# Sheet1.net
KiCad netlist of a schematic drawn in Altium Designer
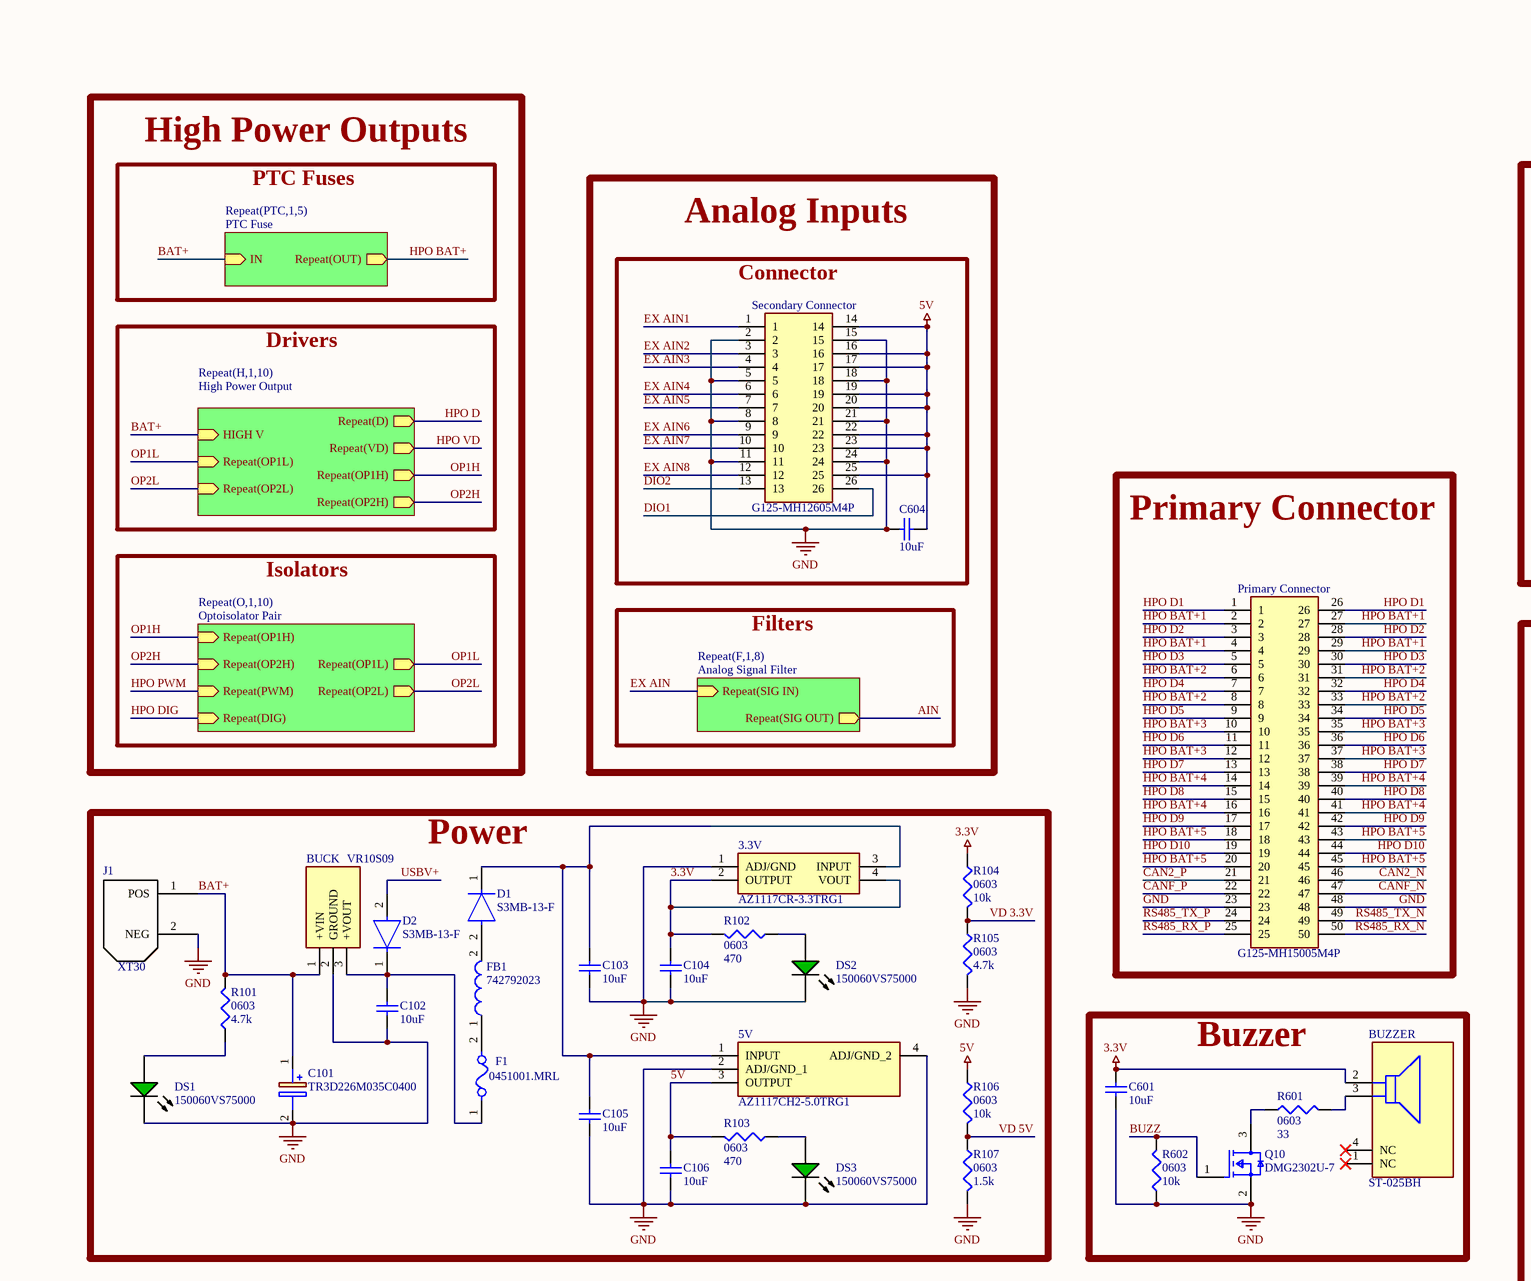
[diagram p0: Sheet1.SchDoc, top left]
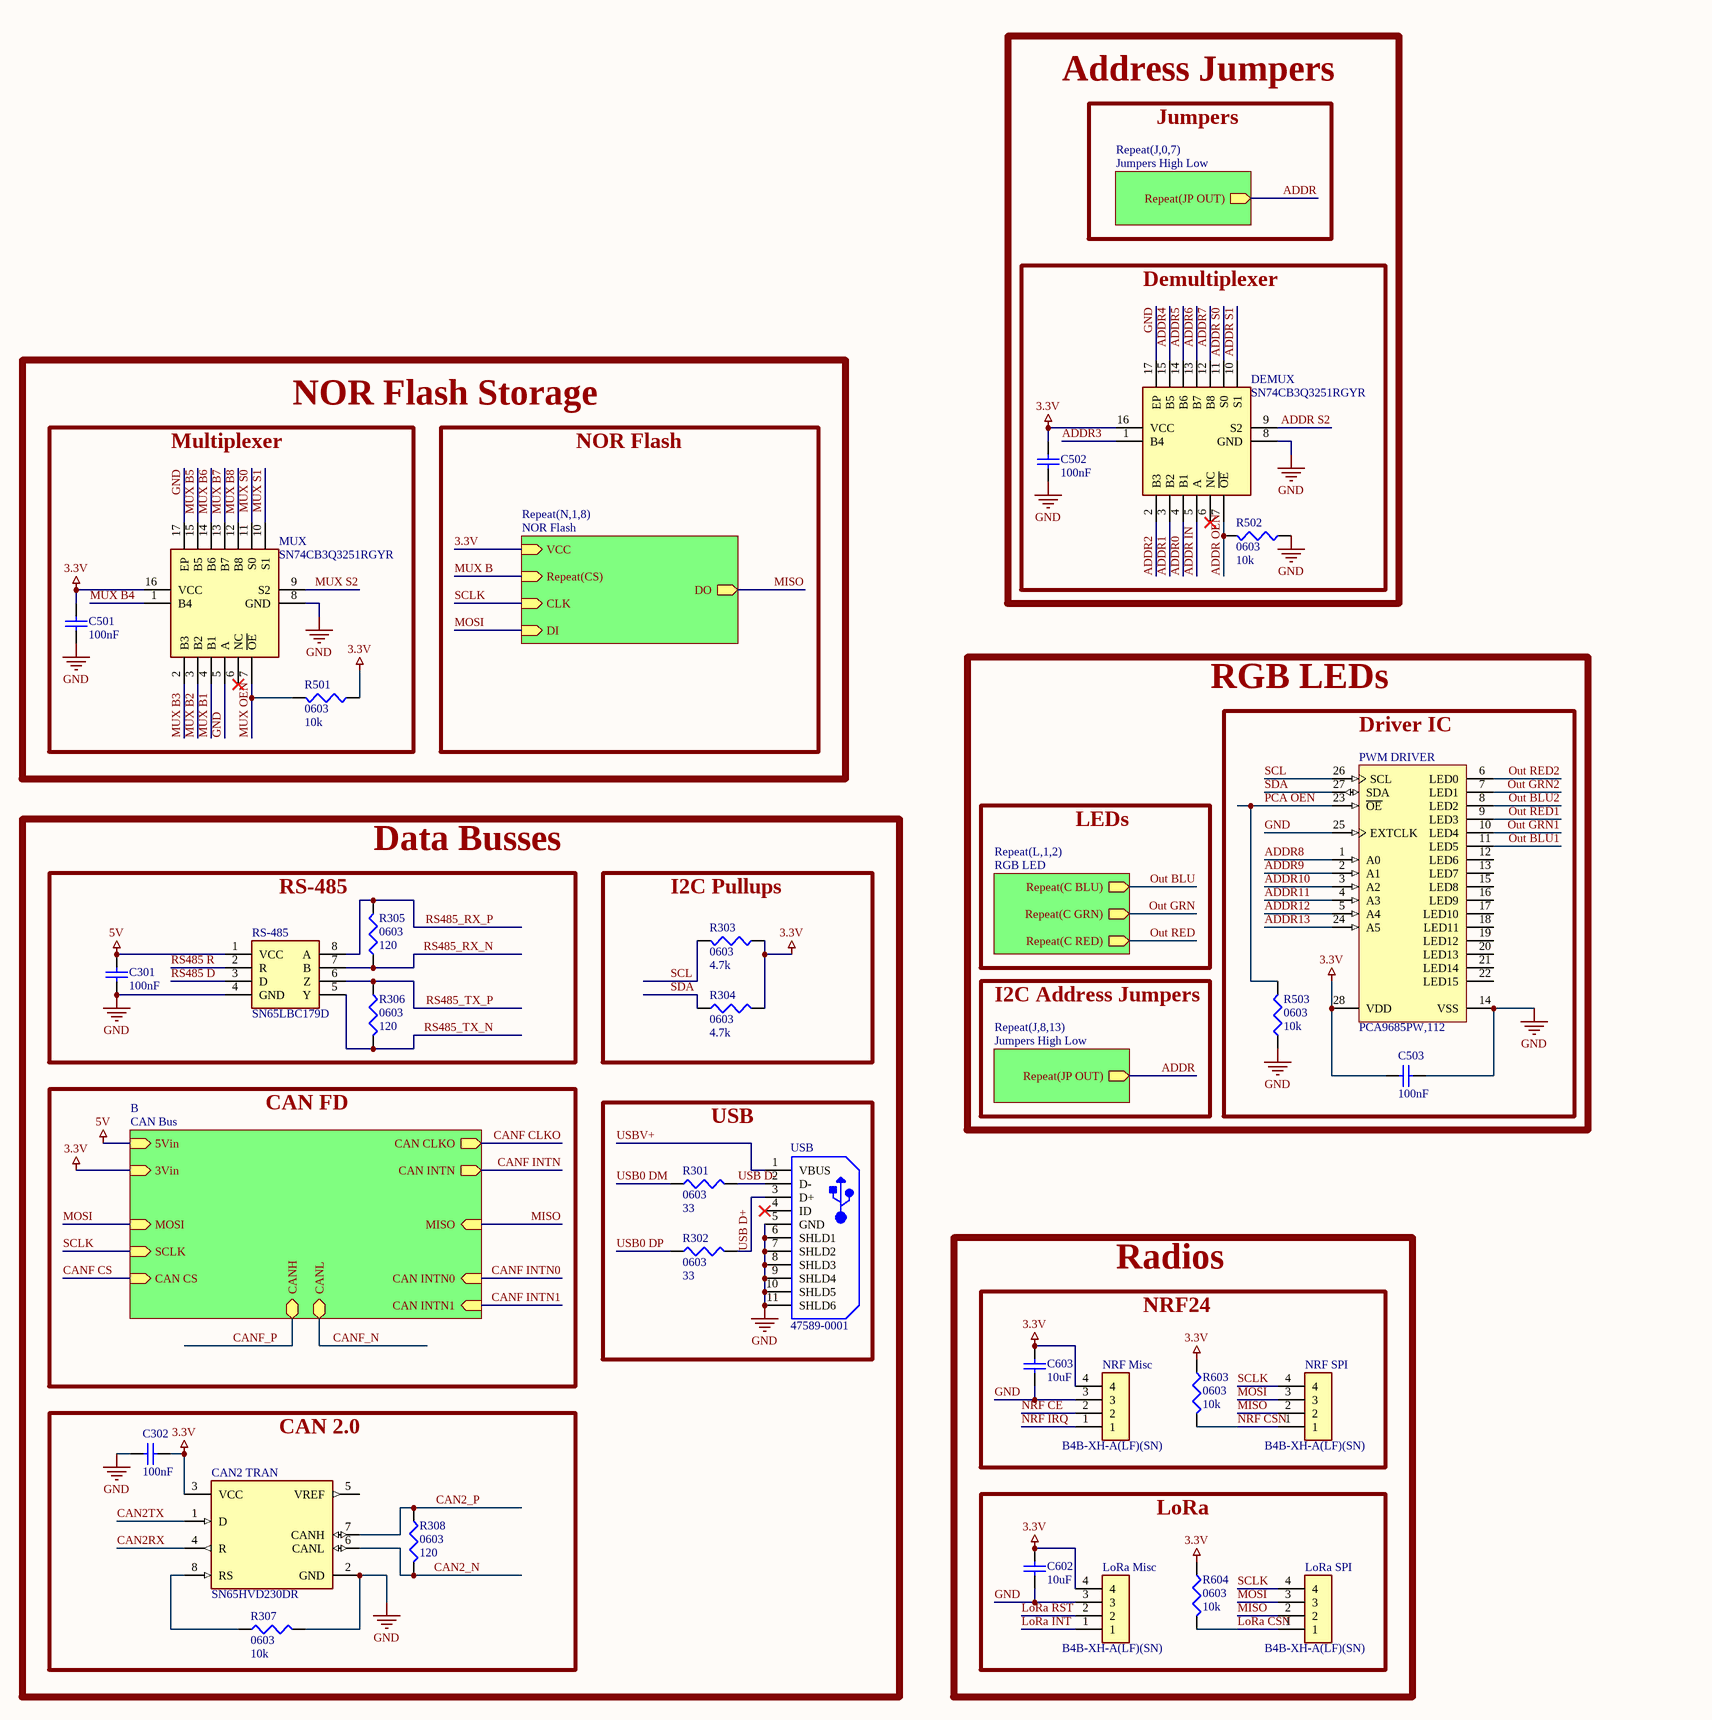
[diagram p1: Sheet1.SchDoc, top right]
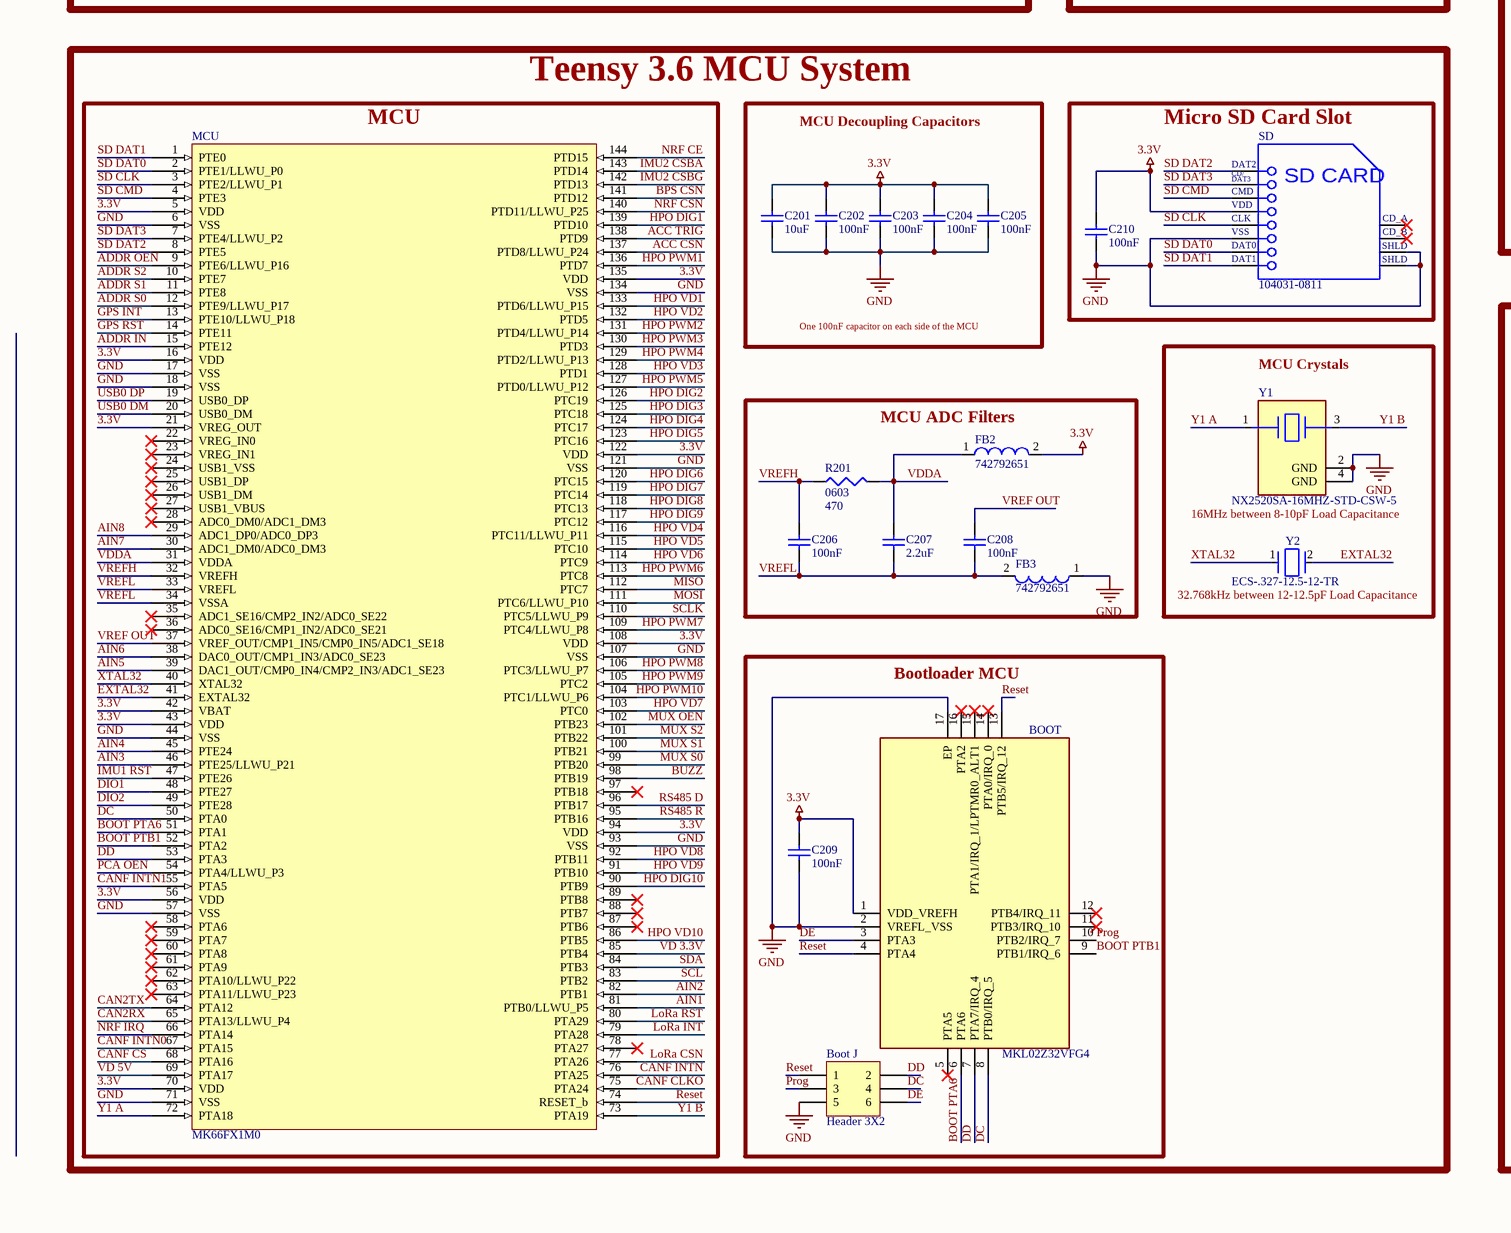
[diagram p2: Sheet1.SchDoc, bottom left]
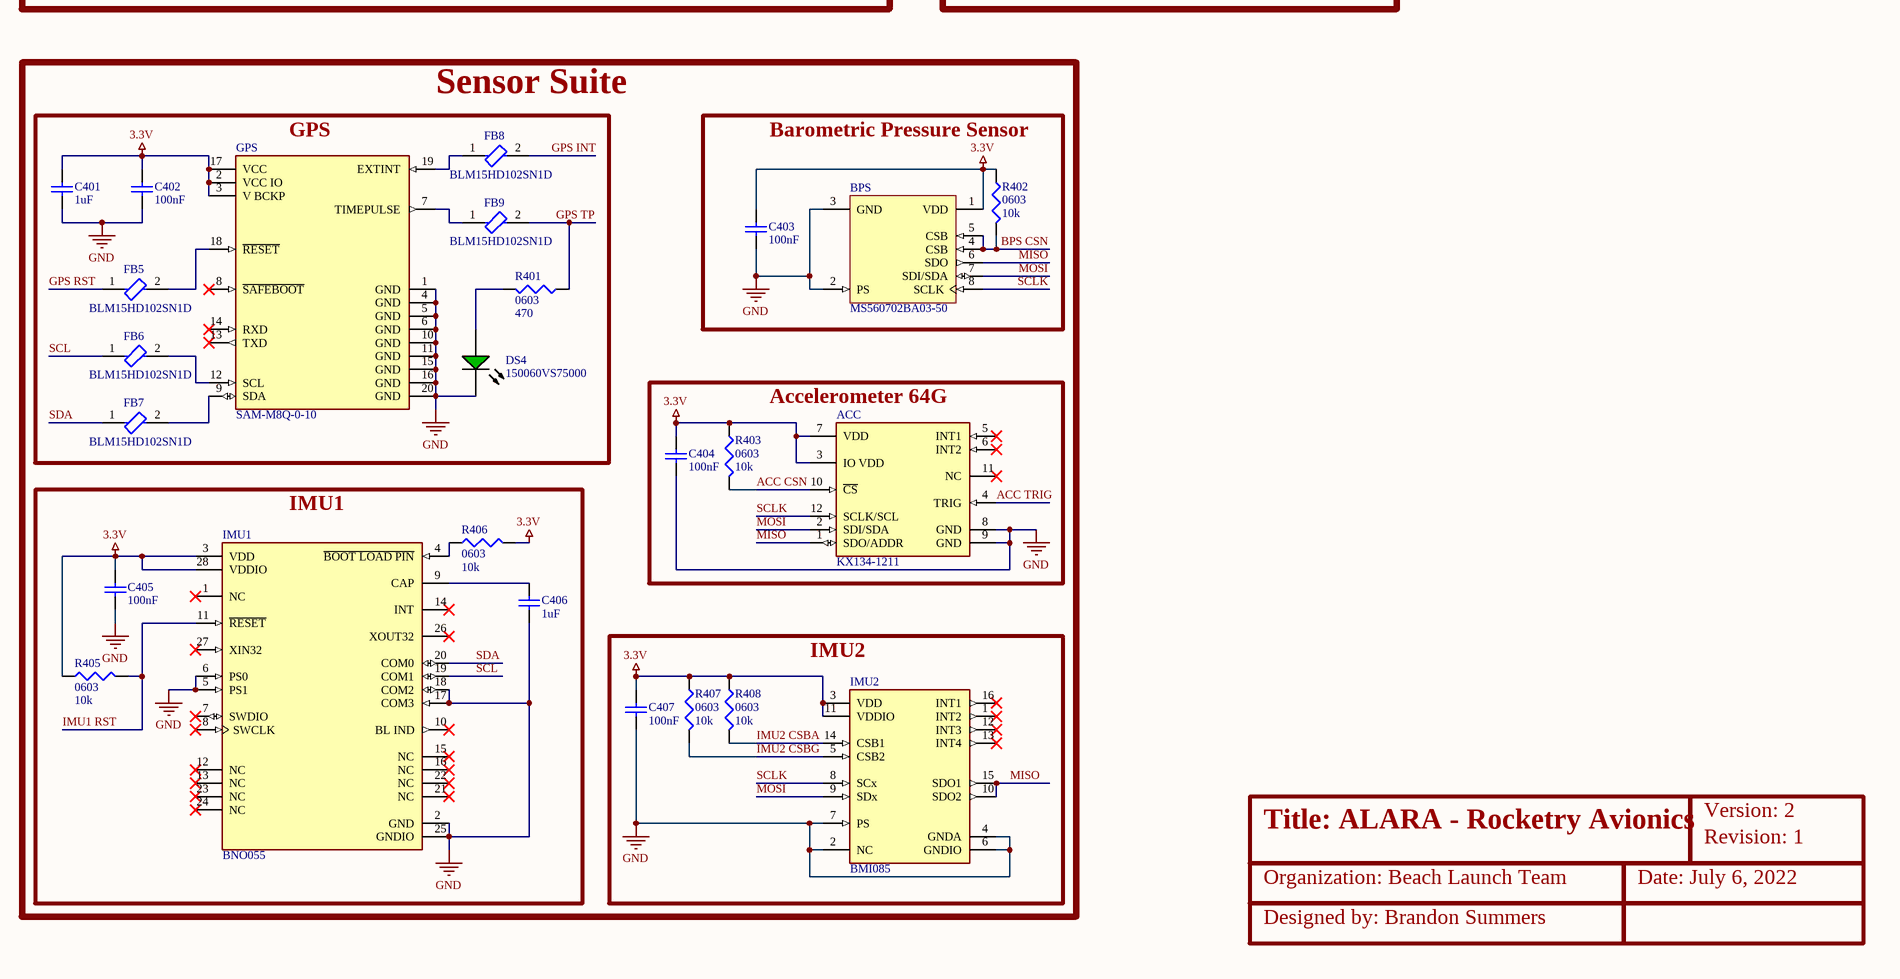
[diagram p3: Sheet1.SchDoc, bottom right]

(export (version "E")
  (design (tool "Eeschema 10.0.6"))
  (components
    (comp (ref "3.3V")
      (value "AZ1117CR-3.3TRG1")
      (footprint "SamacSys:AZ1117CR33TRG1")
      (description "Integrated Circuit")
      (fields (field (name "MOUSER2 PART NUMBER") "621-AZ1117CR-3.3TRG1"))
      (libsource (lib "*") (part "AZ1117CR-3.3TRG1"))
    )
    (comp (ref "5V")
      (value "AZ1117CH2-5.0TRG1")
      (footprint "SamacSys:SOT230P700X180-4N")
      (description "Integrated Circuit")
      (libsource (lib "SamacSys") (part "AZ1117CH2-5.0TRG1"))
    )
    (comp (ref "ACC")
      (value "KX134-1211")
      (footprint "FP-KX134-1211-MFG")
      (description "105C OPERATING HIGHER BANDWIDTH,")
      (libsource (lib "Altium Content Vault") (part "690d2a4d51cffb5fe50aad75ddab18e"))
    )
    (comp (ref "BOOT")
      (value "MKL02Z32VFG4")
      (footprint "SamacSys:QFN50P300X300X65-17N-D")
      (description "Integrated Circuit")
      (fields (field (name "MOUSER PART NUMBER") "841-MKL02Z32VFG4"))
      (libsource (lib "*") (part "MKL02Z32VFG4"))
    )
    (comp (ref "Boot J")
      (value "Header 3X2")
      (footprint "HDR2X3")
      (description "Header, 3-Pin, Dual row")
      (fields (field (name "PUBLISHER") "Altium Limited"))
      (libsource (lib "Miscellaneous Connectors") (part "Header 3X2"))
    )
    (comp (ref "BPS")
      (value "MS560702BA03-50")
      (footprint "TECO-MS560702BA03-50_V")
      (fields (field (name "MANUFACTURER") "TE Connectivity"))
      (libsource (lib "Altium Content Vault") (part "TECO-MS560702BA03-8"))
    )
    (comp (ref "BUCK")
      (value "VR10S09")
      (footprint "SamacSys:VR10S09")
      (description "Power Supply")
      (libsource (lib "SamacSys") (part "VR10S09"))
    )
    (comp (ref "BUZZER")
      (value "ST-025BH")
      (footprint "FP-ST-025BH-MFG")
      (description "AUDIO MAGNETIC XDCR 2-4V SMD")
      (fields
        (field (name "OCTOPART") "https://octopart.com/st-025bh-soberton-22171825")
        (field (name "MANUFACTURER") "Soberton Inc.")
      )
      (libsource (lib "Altium Content Vault") (part "31cc79d7b80ed2267c9b1676827f62c"))
    )
    (comp (ref "C101")
      (value "TR3D226M035C0400")
      (footprint "SamacSys:CAPPM7343X310N")
      (description "Capacitor Polarised")
      (libsource (lib "SamacSys") (part "TR3D226M035C0400"))
    )
    (comp (ref "C102")
      (value "10uF")
      (footprint "CAPC1608X95X40ML15T15")
      (fields (field (name "MANUFACTURER") "Vitramon") (field (name "PART NUMBER") "VJ0603Y104KXQCW1BC"))
      (libsource (lib "Altium Content Vault") (part "CAP"))
    )
    (comp (ref "C103")
      (value "10uF")
      (footprint "CAPC1608X95X40ML15T15")
      (fields (field (name "MANUFACTURER") "Vitramon") (field (name "PART NUMBER") "VJ0603Y104KXQCW1BC"))
      (libsource (lib "Altium Content Vault") (part "CAP"))
    )
    (comp (ref "C104")
      (value "10uF")
      (footprint "CAPC1608X95X40ML15T15")
      (fields (field (name "MANUFACTURER") "Vitramon") (field (name "PART NUMBER") "VJ0603Y104KXQCW1BC"))
      (libsource (lib "Altium Content Vault") (part "CAP"))
    )
    (comp (ref "C105")
      (value "10uF")
      (footprint "CAPC1608X95X40ML15T15")
      (fields (field (name "MANUFACTURER") "Vitramon") (field (name "PART NUMBER") "VJ0603Y104KXQCW1BC"))
      (libsource (lib "Altium Content Vault") (part "CAP"))
    )
    (comp (ref "C106")
      (value "10uF")
      (footprint "CAPC1608X95X40ML15T15")
      (fields (field (name "MANUFACTURER") "Vitramon") (field (name "PART NUMBER") "VJ0603Y104KXQCW1BC"))
      (libsource (lib "Altium Content Vault") (part "CAP"))
    )
    (comp (ref "C201")
      (value "10uF")
      (footprint "CAPC1608X95X40ML15T15")
      (fields (field (name "MANUFACTURER") "Vitramon") (field (name "PART NUMBER") "VJ0603Y104KXQCW1BC"))
      (libsource (lib "Altium Content Vault") (part "CAP"))
    )
    (comp (ref "C202")
      (value "100nF")
      (footprint "CAPC1608X95X40ML15T15")
      (fields (field (name "MANUFACTURER") "Vitramon") (field (name "PART NUMBER") "VJ0603Y104KXQCW1BC"))
      (libsource (lib "Altium Content Vault") (part "CAP"))
    )
    (comp (ref "C203")
      (value "100nF")
      (footprint "CAPC1608X95X40ML15T15")
      (fields (field (name "MANUFACTURER") "Vitramon") (field (name "PART NUMBER") "VJ0603Y104KXQCW1BC"))
      (libsource (lib "Altium Content Vault") (part "CAP"))
    )
    (comp (ref "C204")
      (value "100nF")
      (footprint "CAPC1608X95X40ML15T15")
      (fields (field (name "MANUFACTURER") "Vitramon") (field (name "PART NUMBER") "VJ0603Y104KXQCW1BC"))
      (libsource (lib "Altium Content Vault") (part "CAP"))
    )
    (comp (ref "C205")
      (value "100nF")
      (footprint "CAPC1608X95X40ML15T15")
      (fields (field (name "MANUFACTURER") "Vitramon") (field (name "PART NUMBER") "VJ0603Y104KXQCW1BC"))
      (libsource (lib "Altium Content Vault") (part "CAP"))
    )
    (comp (ref "C206")
      (value "100nF")
      (footprint "CAPC1608X95X40ML15T15")
      (fields (field (name "MANUFACTURER") "Vitramon") (field (name "PART NUMBER") "VJ0603Y104KXQCW1BC"))
      (libsource (lib "Altium Content Vault") (part "CAP"))
    )
    (comp (ref "C207")
      (value "2.2uF")
      (footprint "CAPC1608X95X40ML15T15")
      (fields (field (name "MANUFACTURER") "Vitramon") (field (name "PART NUMBER") "VJ0603Y104KXQCW1BC"))
      (libsource (lib "Altium Content Vault") (part "CAP"))
    )
    (comp (ref "C208")
      (value "100nF")
      (footprint "CAPC1608X95X40ML15T15")
      (fields (field (name "MANUFACTURER") "Vitramon") (field (name "PART NUMBER") "VJ0603Y104KXQCW1BC"))
      (libsource (lib "Altium Content Vault") (part "CAP"))
    )
    (comp (ref "C209")
      (value "100nF")
      (footprint "CAPC1608X95X40ML15T15")
      (fields (field (name "MANUFACTURER") "Vitramon") (field (name "PART NUMBER") "VJ0603Y104KXQCW1BC"))
      (libsource (lib "Altium Content Vault") (part "CAP"))
    )
    (comp (ref "C210")
      (value "100nF")
      (footprint "CAPC1608X95X40ML15T15")
      (fields (field (name "MANUFACTURER") "Vitramon") (field (name "PART NUMBER") "VJ0603Y104KXQCW1BC"))
      (libsource (lib "Altium Content Vault") (part "CAP"))
    )
    (comp (ref "C301")
      (value "100nF")
      (footprint "CAPC1608X95X40ML15T15")
      (fields (field (name "MANUFACTURER") "Vitramon") (field (name "PART NUMBER") "VJ0603Y104KXQCW1BC"))
      (libsource (lib "Altium Content Vault") (part "CAP"))
    )
    (comp (ref "C302")
      (value "100nF")
      (footprint "CAPC1608X95X40ML15T15")
      (fields (field (name "MANUFACTURER") "Vitramon") (field (name "PART NUMBER") "VJ0603Y104KXQCW1BC"))
      (libsource (lib "Altium Content Vault") (part "CAP"))
    )
    (comp (ref "C401")
      (value "1uF")
      (footprint "CAPC1608X95X40ML15T15")
      (fields (field (name "MANUFACTURER") "Vitramon") (field (name "PART NUMBER") "VJ0603Y104KXQCW1BC"))
      (libsource (lib "Altium Content Vault") (part "CAP"))
    )
    (comp (ref "C402")
      (value "100nF")
      (footprint "CAPC1608X95X40ML15T15")
      (fields (field (name "MANUFACTURER") "Vitramon") (field (name "PART NUMBER") "VJ0603Y104KXQCW1BC"))
      (libsource (lib "Altium Content Vault") (part "CAP"))
    )
    (comp (ref "C403")
      (value "100nF")
      (footprint "CAPC1608X95X40ML15T15")
      (fields (field (name "MANUFACTURER") "Vitramon") (field (name "PART NUMBER") "VJ0603Y104KXQCW1BC"))
      (libsource (lib "Altium Content Vault") (part "CAP"))
    )
    (comp (ref "C404")
      (value "100nF")
      (footprint "CAPC1608X95X40ML15T15")
      (fields (field (name "MANUFACTURER") "Vitramon") (field (name "PART NUMBER") "VJ0603Y104KXQCW1BC"))
      (libsource (lib "Altium Content Vault") (part "CAP"))
    )
    (comp (ref "C405")
      (value "100nF")
      (footprint "CAPC1608X95X40ML15T15")
      (fields (field (name "MANUFACTURER") "Vitramon") (field (name "PART NUMBER") "VJ0603Y104KXQCW1BC"))
      (libsource (lib "Altium Content Vault") (part "CAP"))
    )
    (comp (ref "C406")
      (value "1uF")
      (footprint "CAPC1608X95X40ML15T15")
      (fields (field (name "MANUFACTURER") "Vitramon") (field (name "PART NUMBER") "VJ0603Y104KXQCW1BC"))
      (libsource (lib "Altium Content Vault") (part "CAP"))
    )
    (comp (ref "C407")
      (value "100nF")
      (footprint "CAPC1608X95X40ML15T15")
      (fields (field (name "MANUFACTURER") "Vitramon") (field (name "PART NUMBER") "VJ0603Y104KXQCW1BC"))
      (libsource (lib "Altium Content Vault") (part "CAP"))
    )
    (comp (ref "C501")
      (value "100nF")
      (footprint "CAPC1608X95X40ML15T15")
      (fields (field (name "MANUFACTURER") "Vitramon") (field (name "PART NUMBER") "VJ0603Y104KXQCW1BC"))
      (libsource (lib "Altium Content Vault") (part "CAP"))
    )
    (comp (ref "C502")
      (value "100nF")
      (footprint "CAPC1608X95X40ML15T15")
      (fields (field (name "MANUFACTURER") "Vitramon") (field (name "PART NUMBER") "VJ0603Y104KXQCW1BC"))
      (libsource (lib "Altium Content Vault") (part "CAP"))
    )
    (comp (ref "C503")
      (value "100nF")
      (footprint "CAPC1608X95X40ML15T15")
      (fields (field (name "MANUFACTURER") "Vitramon") (field (name "PART NUMBER") "VJ0603Y104KXQCW1BC"))
      (libsource (lib "Altium Content Vault") (part "CAP"))
    )
    (comp (ref "C601")
      (value "10uF")
      (footprint "CAPC1608X95X40ML15T15")
      (fields (field (name "MANUFACTURER") "Vitramon") (field (name "PART NUMBER") "VJ0603Y104KXQCW1BC"))
      (libsource (lib "Altium Content Vault") (part "CAP"))
    )
    (comp (ref "C602")
      (value "10uF")
      (footprint "CAPC1608X95X40ML15T15")
      (fields (field (name "MANUFACTURER") "Vitramon") (field (name "PART NUMBER") "VJ0603Y104KXQCW1BC"))
      (libsource (lib "Altium Content Vault") (part "CAP"))
    )
    (comp (ref "C603")
      (value "10uF")
      (footprint "CAPC1608X95X40ML15T15")
      (fields (field (name "MANUFACTURER") "Vitramon") (field (name "PART NUMBER") "VJ0603Y104KXQCW1BC"))
      (libsource (lib "Altium Content Vault") (part "CAP"))
    )
    (comp (ref "C604")
      (value "10uF")
      (footprint "CAPC1608X95X40ML15T15")
      (fields (field (name "MANUFACTURER") "Vitramon") (field (name "PART NUMBER") "VJ0603Y104KXQCW1BC"))
      (libsource (lib "Altium Content Vault") (part "CAP"))
    )
    (comp (ref "CAN2 TRAN")
      (value "SN65HVD230DR")
      (footprint "FP-D0008A-IPC_A")
      (description "IC TRANSCEIVER HALF 1/1 8SOIC")
      (libsource (lib "Altium Content Vault") (part "43b56812b1adf0e60a7acfb7c27ab91"))
    )
    (comp (ref "D1")
      (value "S3MB-13-F")
      (footprint "FP-SMB-MFG")
      (description "DIODE GEN PURP 1KV 3A SMB")
      (fields
        (field (name "MANUFACTURER") "Diodes Inc.")
        (field (name "OCTOPART") "https://octopart.com/s3mb-13-f-diodes+inc.-333387")
      )
      (libsource (lib "Altium Content Vault") (part "d7152d700b627762746794eb795d46e"))
    )
    (comp (ref "D2")
      (value "S3MB-13-F")
      (footprint "FP-SMB-MFG")
      (description "DIODE GEN PURP 1KV 3A SMB")
      (fields
        (field (name "MANUFACTURER") "Diodes Inc.")
        (field (name "OCTOPART") "https://octopart.com/s3mb-13-f-diodes+inc.-333387")
      )
      (libsource (lib "Altium Content Vault") (part "d7152d700b627762746794eb795d46e"))
    )
    (comp (ref "DEMUX")
      (value "SN74CB3Q3251RGYR")
      (footprint "SamacSys:SN74CBT3257CRGYR")
      (description "Integrated Circuit")
      (libsource (lib "*") (part "SN74CB3Q3251RGYR"))
    )
    (comp (ref "DS1")
      (value "150060VS75000")
      (footprint "WE-150060VS75000_V")
      (libsource (lib "Altium Content Vault") (part "LED_GREEN_K1A2-2"))
    )
    (comp (ref "DS2")
      (value "150060VS75000")
      (footprint "WE-150060VS75000_V")
      (libsource (lib "Altium Content Vault") (part "LED_GREEN_K1A2-2"))
    )
    (comp (ref "DS3")
      (value "150060VS75000")
      (footprint "WE-150060VS75000_V")
      (libsource (lib "Altium Content Vault") (part "LED_GREEN_K1A2-2"))
    )
    (comp (ref "DS4")
      (value "150060VS75000")
      (footprint "WE-150060VS75000_V")
      (libsource (lib "Altium Content Vault") (part "LED_GREEN_K1A2-2"))
    )
    (comp (ref "F1")
      (value "0451001.MRL")
      (footprint "FP-0451-MFG")
      (description "FUSE BRD MNT 1A 125VAC/VDC 2SMD")
      (fields
        (field (name "OCTOPART") "https://octopart.com/0451001.mrl-littelfuse-566368")
        (field (name "MANUFACTURER") "Littelfuse Inc")
      )
      (libsource (lib "Altium Content Vault") (part "5bcf9b9f640e542cf0359d10258e979"))
    )
    (comp (ref "FB1")
      (value "742792023")
      (footprint "SMD-0805")
      (description "SMD EMI Suppression Ferrite Bead WE-CBF, Z = 120 Ohm")
      (libsource (lib "Altium Content Vault") (part "PAS-IND-INDUCTOR-2"))
    )
    (comp (ref "FB2")
      (value "742792651")
      (footprint "SMD-0603")
      (description "SMD EMI Suppression Ferrite Bead WE-CBF, Z = 600 Ohm")
      (libsource (lib "Altium Content Vault") (part "PAS-IND-INDUCTOR-2"))
    )
    (comp (ref "FB3")
      (value "742792651")
      (footprint "SMD-0603")
      (description "SMD EMI Suppression Ferrite Bead WE-CBF, Z = 600 Ohm")
      (libsource (lib "Altium Content Vault") (part "PAS-IND-INDUCTOR-2"))
    )
    (comp (ref "FB5")
      (value "BLM15HD102SN1D")
      (footprint "FP-BLM15-0_05-IPC_C")
      (description "Chip Ferrite Bead, 0402, 1000Ω @ 100MHz, 1.25Ω, 25%, 250mA")
      (fields (field (name "TOLERANCE") "25%"))
      (libsource (lib "Altium Content Vault") (part "5f30dd21d616792df468990f7003faa"))
    )
    (comp (ref "FB6")
      (value "BLM15HD102SN1D")
      (footprint "FP-BLM15-0_05-IPC_C")
      (description "Chip Ferrite Bead, 0402, 1000Ω @ 100MHz, 1.25Ω, 25%, 250mA")
      (fields (field (name "TOLERANCE") "25%"))
      (libsource (lib "Altium Content Vault") (part "5f30dd21d616792df468990f7003faa"))
    )
    (comp (ref "FB7")
      (value "BLM15HD102SN1D")
      (footprint "FP-BLM15-0_05-IPC_C")
      (description "Chip Ferrite Bead, 0402, 1000Ω @ 100MHz, 1.25Ω, 25%, 250mA")
      (fields (field (name "TOLERANCE") "25%"))
      (libsource (lib "Altium Content Vault") (part "5f30dd21d616792df468990f7003faa"))
    )
    (comp (ref "FB8")
      (value "BLM15HD102SN1D")
      (footprint "FP-BLM15-0_05-IPC_C")
      (description "Chip Ferrite Bead, 0402, 1000Ω @ 100MHz, 1.25Ω, 25%, 250mA")
      (fields (field (name "TOLERANCE") "25%"))
      (libsource (lib "Altium Content Vault") (part "5f30dd21d616792df468990f7003faa"))
    )
    (comp (ref "FB9")
      (value "BLM15HD102SN1D")
      (footprint "FP-BLM15-0_05-IPC_C")
      (description "Chip Ferrite Bead, 0402, 1000Ω @ 100MHz, 1.25Ω, 25%, 250mA")
      (fields (field (name "TOLERANCE") "25%"))
      (libsource (lib "Altium Content Vault") (part "5f30dd21d616792df468990f7003faa"))
    )
    (comp (ref "GPS")
      (value "SAM-M8Q-0-10")
      (footprint "FP-SAM-M8Q-0-10-MFG")
      (description "RF RX GALILEO 1.575GHZ/1.602GHZ")
      (fields
        (field (name "MANUFACTURER") "uBlox")
        (field (name "OCTOPART") "https://octopart.com/sam-m8q-0-10-u-blox-88247750")
      )
      (libsource (lib "Altium Content Vault") (part "e897669bc61729ed63f6e62e0b1e840"))
    )
    (comp (ref "IMU1")
      (value "BNO055")
      (footprint "FP-BNO055-MFG")
      (description "IMU ACCEL/GYRO/MAG I2C 28LGA")
      (libsource (lib "Altium Content Vault") (part "ba837af00a0b6167256f888b31462b1"))
    )
    (comp (ref "IMU2")
      (value "BMI085")
      (footprint "FP-BMI055-MFG")
      (description "IMU ACCEL/GYRO I2C/SPI 16LGA")
      (libsource (lib "Altium Content Vault") (part "27928433b13d6d742e94b461c0d61b2"))
    )
    (comp (ref "J1") (value "XT30") (footprint "XT30") (libsource (lib "XT30") (part "XT30")))
    (comp (ref "LoRa Misc")
      (value "B4B-XH-A(LF)(SN)")
      (footprint "JST_B4B-XH-A(LF)(SN)")
      (description "XH Series 4 Position 2.5 mm Pitch Through Hole Crimp Top Entry Shrouded Header")
      (fields (field (name "MF") "{'manufacturer': u'JST Sales America Inc.'}"))
      (libsource (lib "SnapEDA_Library") (part "B4B-XH-A(LF)(SN)"))
    )
    (comp (ref "LoRa SPI")
      (value "B4B-XH-A(LF)(SN)")
      (footprint "JST_B4B-XH-A(LF)(SN)")
      (description "XH Series 4 Position 2.5 mm Pitch Through Hole Crimp Top Entry Shrouded Header")
      (fields (field (name "MF") "{'manufacturer': u'JST Sales America Inc.'}"))
      (libsource (lib "SnapEDA_Library") (part "B4B-XH-A(LF)(SN)"))
    )
    (comp (ref "MCU")
      (value "MK66FX1M0")
      (footprint "LQFP144 0.5mm Pitch")
      (libsource (lib "MK66FX1M0VLQ18") (part "COMPONENT_1"))
    )
    (comp (ref "MUX")
      (value "SN74CB3Q3251RGYR")
      (footprint "SamacSys:SN74CBT3257CRGYR")
      (description "Integrated Circuit")
      (libsource (lib "*") (part "SN74CB3Q3251RGYR"))
    )
    (comp (ref "NRF Misc")
      (value "B4B-XH-A(LF)(SN)")
      (footprint "JST_B4B-XH-A(LF)(SN)")
      (description "XH Series 4 Position 2.5 mm Pitch Through Hole Crimp Top Entry Shrouded Header")
      (fields (field (name "MF") "{'manufacturer': u'JST Sales America Inc.'}"))
      (libsource (lib "SnapEDA_Library") (part "B4B-XH-A(LF)(SN)"))
    )
    (comp (ref "NRF SPI")
      (value "B4B-XH-A(LF)(SN)")
      (footprint "JST_B4B-XH-A(LF)(SN)")
      (description "XH Series 4 Position 2.5 mm Pitch Through Hole Crimp Top Entry Shrouded Header")
      (fields (field (name "MF") "{'manufacturer': u'JST Sales America Inc.'}"))
      (libsource (lib "SnapEDA_Library") (part "B4B-XH-A(LF)(SN)"))
    )
    (comp (ref "Primary Connector")
      (value "G125-MH15005M4P")
      (footprint "SamacSys:G125-MH15005M4P")
      (description "Connector")
      (fields (field (name "MOUSER PART NUMBER") "855-G125MH1505M4PM4P"))
      (libsource (lib "SamacSys") (part "G125-MH15005M4P"))
    )
    (comp (ref "PWM DRIVER")
      (value "PCA9685PW,112")
      (footprint "SOT361-1_V")
      (fields (field (name "PARTNUMBER") "PCA9685"))
      (libsource (lib "Altium Content Vault") (part "NXP-PCA9685-SOT361-1"))
    )
    (comp (ref "Q10")
      (value "DMG2302U-7")
      (footprint "FP-SOT23-MFG")
      (description "MOSFET N-CH 20V 4.2A SOT23")
      (libsource (lib "Altium Content Vault") (part "381a366367e4312d0f7d2747150cb42"))
    )
    (comp (ref "R101")
      (value "0603")
      (footprint "J1-0603")
      (description "Resistor")
      (fields (field (name "ALTIUM_VALUE") "4.7k") (field (name "PUBLISHER") "Altium Limited"))
      (libsource (lib "Miscellaneous Devices") (part "Res3"))
    )
    (comp (ref "R102")
      (value "0603")
      (footprint "J1-0603")
      (description "Resistor")
      (fields (field (name "ALTIUM_VALUE") "470") (field (name "PUBLISHER") "Altium Limited"))
      (libsource (lib "Miscellaneous Devices") (part "Res3"))
    )
    (comp (ref "R103")
      (value "0603")
      (footprint "J1-0603")
      (description "Resistor")
      (fields (field (name "ALTIUM_VALUE") "470") (field (name "PUBLISHER") "Altium Limited"))
      (libsource (lib "Miscellaneous Devices") (part "Res3"))
    )
    (comp (ref "R104")
      (value "0603")
      (footprint "J1-0603")
      (description "Resistor")
      (fields (field (name "ALTIUM_VALUE") "10k") (field (name "PUBLISHER") "Altium Limited"))
      (libsource (lib "Miscellaneous Devices") (part "Res3"))
    )
    (comp (ref "R105")
      (value "0603")
      (footprint "J1-0603")
      (description "Resistor")
      (fields (field (name "ALTIUM_VALUE") "4.7k") (field (name "PUBLISHER") "Altium Limited"))
      (libsource (lib "Miscellaneous Devices") (part "Res3"))
    )
    (comp (ref "R106")
      (value "0603")
      (footprint "J1-0603")
      (description "Resistor")
      (fields (field (name "ALTIUM_VALUE") "10k") (field (name "PUBLISHER") "Altium Limited"))
      (libsource (lib "Miscellaneous Devices") (part "Res3"))
    )
    (comp (ref "R107")
      (value "0603")
      (footprint "J1-0603")
      (description "Resistor")
      (fields (field (name "ALTIUM_VALUE") "1.5k") (field (name "PUBLISHER") "Altium Limited"))
      (libsource (lib "Miscellaneous Devices") (part "Res3"))
    )
    (comp (ref "R201")
      (value "0603")
      (footprint "J1-0603")
      (description "Resistor")
      (fields (field (name "ALTIUM_VALUE") "470") (field (name "PUBLISHER") "Altium Limited"))
      (libsource (lib "Miscellaneous Devices") (part "Res3"))
    )
    (comp (ref "R301")
      (value "0603")
      (footprint "J1-0603")
      (description "Resistor")
      (fields (field (name "ALTIUM_VALUE") "33") (field (name "PUBLISHER") "Altium Limited"))
      (libsource (lib "Miscellaneous Devices") (part "Res3"))
    )
    (comp (ref "R302")
      (value "0603")
      (footprint "J1-0603")
      (description "Resistor")
      (fields (field (name "ALTIUM_VALUE") "33") (field (name "PUBLISHER") "Altium Limited"))
      (libsource (lib "Miscellaneous Devices") (part "Res3"))
    )
    (comp (ref "R303")
      (value "0603")
      (footprint "J1-0603")
      (description "Resistor")
      (fields (field (name "ALTIUM_VALUE") "4.7k") (field (name "PUBLISHER") "Altium Limited"))
      (libsource (lib "Miscellaneous Devices") (part "Res3"))
    )
    (comp (ref "R304")
      (value "0603")
      (footprint "J1-0603")
      (description "Resistor")
      (fields (field (name "ALTIUM_VALUE") "4.7k") (field (name "PUBLISHER") "Altium Limited"))
      (libsource (lib "Miscellaneous Devices") (part "Res3"))
    )
    (comp (ref "R305")
      (value "0603")
      (footprint "J1-0603")
      (description "Resistor")
      (fields (field (name "ALTIUM_VALUE") "120") (field (name "PUBLISHER") "Altium Limited"))
      (libsource (lib "Miscellaneous Devices") (part "Res3"))
    )
    (comp (ref "R306")
      (value "0603")
      (footprint "J1-0603")
      (description "Resistor")
      (fields (field (name "ALTIUM_VALUE") "120") (field (name "PUBLISHER") "Altium Limited"))
      (libsource (lib "Miscellaneous Devices") (part "Res3"))
    )
    (comp (ref "R307")
      (value "0603")
      (footprint "J1-0603")
      (description "Resistor")
      (fields (field (name "ALTIUM_VALUE") "10k") (field (name "PUBLISHER") "Altium Limited"))
      (libsource (lib "Miscellaneous Devices") (part "Res3"))
    )
    (comp (ref "R308")
      (value "0603")
      (footprint "J1-0603")
      (description "Resistor")
      (fields (field (name "ALTIUM_VALUE") "120") (field (name "PUBLISHER") "Altium Limited"))
      (libsource (lib "Miscellaneous Devices") (part "Res3"))
    )
    (comp (ref "R401")
      (value "0603")
      (footprint "J1-0603")
      (description "Resistor")
      (fields (field (name "ALTIUM_VALUE") "470") (field (name "PUBLISHER") "Altium Limited"))
      (libsource (lib "Miscellaneous Devices") (part "Res3"))
    )
    (comp (ref "R402")
      (value "0603")
      (footprint "J1-0603")
      (description "Resistor")
      (fields (field (name "ALTIUM_VALUE") "10k") (field (name "PUBLISHER") "Altium Limited"))
      (libsource (lib "Miscellaneous Devices") (part "Res3"))
    )
    (comp (ref "R403")
      (value "0603")
      (footprint "J1-0603")
      (description "Resistor")
      (fields (field (name "ALTIUM_VALUE") "10k") (field (name "PUBLISHER") "Altium Limited"))
      (libsource (lib "Miscellaneous Devices") (part "Res3"))
    )
    (comp (ref "R405")
      (value "0603")
      (footprint "J1-0603")
      (description "Resistor")
      (fields (field (name "ALTIUM_VALUE") "10k") (field (name "PUBLISHER") "Altium Limited"))
      (libsource (lib "Miscellaneous Devices") (part "Res3"))
    )
    (comp (ref "R406")
      (value "0603")
      (footprint "J1-0603")
      (description "Resistor")
      (fields (field (name "ALTIUM_VALUE") "10k") (field (name "PUBLISHER") "Altium Limited"))
      (libsource (lib "Miscellaneous Devices") (part "Res3"))
    )
    (comp (ref "R407")
      (value "0603")
      (footprint "J1-0603")
      (description "Resistor")
      (fields (field (name "ALTIUM_VALUE") "10k") (field (name "PUBLISHER") "Altium Limited"))
      (libsource (lib "Miscellaneous Devices") (part "Res3"))
    )
    (comp (ref "R408")
      (value "0603")
      (footprint "J1-0603")
      (description "Resistor")
      (fields (field (name "ALTIUM_VALUE") "10k") (field (name "PUBLISHER") "Altium Limited"))
      (libsource (lib "Miscellaneous Devices") (part "Res3"))
    )
    (comp (ref "R501")
      (value "0603")
      (footprint "J1-0603")
      (description "Resistor")
      (fields (field (name "ALTIUM_VALUE") "10k") (field (name "PUBLISHER") "Altium Limited"))
      (libsource (lib "Miscellaneous Devices") (part "Res3"))
    )
    (comp (ref "R502")
      (value "0603")
      (footprint "J1-0603")
      (description "Resistor")
      (fields (field (name "ALTIUM_VALUE") "10k") (field (name "PUBLISHER") "Altium Limited"))
      (libsource (lib "Miscellaneous Devices") (part "Res3"))
    )
    (comp (ref "R503")
      (value "0603")
      (footprint "J1-0603")
      (description "Resistor")
      (fields (field (name "ALTIUM_VALUE") "10k") (field (name "PUBLISHER") "Altium Limited"))
      (libsource (lib "Miscellaneous Devices") (part "Res3"))
    )
    (comp (ref "R601")
      (value "0603")
      (footprint "J1-0603")
      (description "Resistor")
      (fields (field (name "ALTIUM_VALUE") "33") (field (name "PUBLISHER") "Altium Limited"))
      (libsource (lib "Miscellaneous Devices") (part "Res3"))
    )
    (comp (ref "R602")
      (value "0603")
      (footprint "J1-0603")
      (description "Resistor")
      (fields (field (name "ALTIUM_VALUE") "10k") (field (name "PUBLISHER") "Altium Limited"))
      (libsource (lib "Miscellaneous Devices") (part "Res3"))
    )
    (comp (ref "R603")
      (value "0603")
      (footprint "J1-0603")
      (description "Resistor")
      (fields (field (name "ALTIUM_VALUE") "10k") (field (name "PUBLISHER") "Altium Limited"))
      (libsource (lib "Miscellaneous Devices") (part "Res3"))
    )
    (comp (ref "R604")
      (value "0603")
      (footprint "J1-0603")
      (description "Resistor")
      (fields (field (name "ALTIUM_VALUE") "10k") (field (name "PUBLISHER") "Altium Limited"))
      (libsource (lib "Miscellaneous Devices") (part "Res3"))
    )
    (comp (ref "RS-485")
      (value "SN65LBC179D")
      (footprint "SamacSys:SOIC127P600X175-8N")
      (description "Integrated Circuit")
      (libsource (lib "*") (part "SN65LBC179D"))
    )
    (comp (ref "SD")
      (value "104031-0811")
      (footprint "MOLX-104031-0811_V")
      (description "Micro SD Card, RA, -25 to 85 degC, 8-Pin SMD, RoHS, Tape and Reel")
      (fields (field (name "MANUFACTURER") "Molex"))
      (libsource (lib "Altium Content Vault") (part "CN-SD-8-2SW-2S"))
    )
    (comp (ref "Secondary Connector")
      (value "G125-MH12605M4P")
      (footprint "SamacSys:G125-MH12605M4P")
      (description "Connector")
      (fields (field (name "MOUSER PART NUMBER") "855-G125MH1265M4PM4P"))
      (libsource (lib "SamacSys") (part "G125-MH12605M4P"))
    )
    (comp (ref "USB")
      (value "47589-0001")
      (footprint "MOLX-47589-0001_V")
      (description "Right Angle Female Type AB Micro USB Connector, 30 V, 1.8 A, -30 to 85 degC, RoHS, Tape and Reel")
      (fields (field (name "MANUFACTURER") "Molex"))
      (libsource (lib "Altium Content Vault") (part "USB-5-6SHLD"))
    )
    (comp (ref "Y1")
      (value "NX2520SA-16MHZ-STD-CSW-5")
      (footprint "FP-NX2520SA-MFG")
      (description "CRYSTAL 16.0000MHZ 8PF SMD")
      (libsource (lib "Altium Content Vault") (part "07cd68334262f73c450eeb7a763f26b"))
    )
    (comp (ref "Y2")
      (value "ECS-.327-12.5-12-TR")
      (footprint "FP-ECX-12-MFG")
      (description "CRYSTAL 32.7680KHZ 12.5PF SMD")
      (fields (field (name "TOLERANCE") "20ppm"))
      (libsource (lib "Altium Content Vault") (part "99724985039315a44fd0d1401b84e49"))
    )
  )
  (nets
    (net (code "1") (name "/ACC CSN") (class "Default")
      (node (ref "ACC") (pin "10") (pinfunction "~{CS}_10") (pintype "input"))
      (node (ref "MCU") (pin "137") (pinfunction "PTD8/LLWU_P24_137") (pintype "input"))
      (node (ref "R403") (pin "2") (pinfunction "2_2") (pintype "passive"))
    )
    (net (code "2") (name "/ACC TRIG") (class "Default")
      (node (ref "ACC") (pin "4") (pinfunction "TRIG_4") (pintype "input"))
      (node (ref "MCU") (pin "138") (pinfunction "PTD9_138") (pintype "input"))
    )
    (net (code "4") (name "/ADDR IN") (class "Default")
      (node (ref "DEMUX") (pin "5") (pinfunction "A_5") (pintype "passive"))
      (node (ref "MCU") (pin "15") (pinfunction "PTE12_15") (pintype "input"))
    )
    (net (code "5") (name "/ADDR OEN") (class "Default")
      (node (ref "DEMUX") (pin "7") (pinfunction "~{OE}_7") (pintype "passive"))
      (node (ref "MCU") (pin "9") (pinfunction "PTE6/LLWU_P16_9") (pintype "input"))
      (node (ref "R502") (pin "2") (pinfunction "2_2") (pintype "passive"))
    )
    (net (code "6") (name "/ADDR S0") (class "Default")
      (node (ref "DEMUX") (pin "11") (pinfunction "S0_11") (pintype "passive"))
      (node (ref "MCU") (pin "12") (pinfunction "PTE9/LLWU_P17_12") (pintype "input"))
    )
    (net (code "7") (name "/ADDR S1") (class "Default")
      (node (ref "DEMUX") (pin "10") (pinfunction "S1_10") (pintype "passive"))
      (node (ref "MCU") (pin "11") (pinfunction "PTE8_11") (pintype "input"))
    )
    (net (code "8") (name "/ADDR S2") (class "Default")
      (node (ref "DEMUX") (pin "9") (pinfunction "S2_9") (pintype "passive"))
      (node (ref "MCU") (pin "10") (pinfunction "PTE7_10") (pintype "input"))
    )
    (net (code "9") (name "/ADDR0") (class "Default")
      (node (ref "DEMUX") (pin "4") (pinfunction "B1_4") (pintype "passive"))
    )
    (net (code "10") (name "/ADDR1") (class "Default")
      (node (ref "DEMUX") (pin "3") (pinfunction "B2_3") (pintype "passive"))
    )
    (net (code "11") (name "/ADDR2") (class "Default")
      (node (ref "DEMUX") (pin "2") (pinfunction "B3_2") (pintype "passive"))
    )
    (net (code "12") (name "/ADDR3") (class "Default")
      (node (ref "DEMUX") (pin "1") (pinfunction "B4_1") (pintype "passive"))
    )
    (net (code "13") (name "/ADDR4") (class "Default")
      (node (ref "DEMUX") (pin "15") (pinfunction "B5_15") (pintype "passive"))
    )
    (net (code "14") (name "/ADDR5") (class "Default")
      (node (ref "DEMUX") (pin "14") (pinfunction "B6_14") (pintype "passive"))
    )
    (net (code "15") (name "/ADDR6") (class "Default")
      (node (ref "DEMUX") (pin "13") (pinfunction "B7_13") (pintype "passive"))
    )
    (net (code "16") (name "/ADDR7") (class "Default")
      (node (ref "DEMUX") (pin "12") (pinfunction "B8_12") (pintype "passive"))
    )
    (net (code "17") (name "/ADDR8") (class "Default")
      (node (ref "PWM DRIVER") (pin "1") (pinfunction "A0_1") (pintype "input"))
    )
    (net (code "18") (name "/ADDR9") (class "Default")
      (node (ref "PWM DRIVER") (pin "2") (pinfunction "A1_2") (pintype "input"))
    )
    (net (code "19") (name "/ADDR10") (class "Default")
      (node (ref "PWM DRIVER") (pin "3") (pinfunction "A2_3") (pintype "input"))
    )
    (net (code "20") (name "/ADDR11") (class "Default")
      (node (ref "PWM DRIVER") (pin "4") (pinfunction "A3_4") (pintype "input"))
    )
    (net (code "21") (name "/ADDR12") (class "Default")
      (node (ref "PWM DRIVER") (pin "5") (pinfunction "A4_5") (pintype "input"))
    )
    (net (code "22") (name "/ADDR13") (class "Default")
      (node (ref "PWM DRIVER") (pin "24") (pinfunction "A5_24") (pintype "input"))
    )
    (net (code "24") (name "/AIN1") (class "Default")
      (node (ref "MCU") (pin "81") (pinfunction "PTB0/LLWU_P5_81") (pintype "input"))
    )
    (net (code "25") (name "/AIN2") (class "Default")
      (node (ref "MCU") (pin "82") (pinfunction "PTB1_82") (pintype "input"))
    )
    (net (code "26") (name "/AIN3") (class "Default")
      (node (ref "MCU") (pin "46") (pinfunction "PTE25/LLWU_P21_46") (pintype "input"))
    )
    (net (code "27") (name "/AIN4") (class "Default")
      (node (ref "MCU") (pin "45") (pinfunction "PTE24_45") (pintype "input"))
    )
    (net (code "28") (name "/AIN5") (class "Default")
      (node (ref "MCU") (pin "39") (pinfunction "DAC1_OUT/CMP0_IN4/CMP2_IN3/ADC1_SE23_39") (pintype "input"))
    )
    (net (code "29") (name "/AIN6") (class "Default")
      (node (ref "MCU") (pin "38") (pinfunction "DAC0_OUT/CMP1_IN3/ADC0_SE23_38") (pintype "input"))
    )
    (net (code "30") (name "/AIN7") (class "Default")
      (node (ref "MCU") (pin "30") (pinfunction "ADC1_DM0/ADC0_DM3_30") (pintype "input"))
    )
    (net (code "31") (name "/AIN8") (class "Default")
      (node (ref "MCU") (pin "29") (pinfunction "ADC1_DP0/ADC0_DP3_29") (pintype "input"))
    )
    (net (code "32") (name "/BAT+") (class "Default")
      (node (ref "BUCK") (pin "1") (pinfunction "+VIN_1") (pintype "passive"))
      (node (ref "C101") (pin "1") (pinfunction "+_1") (pintype "passive"))
      (node (ref "J1") (pin "1") (pinfunction "POS_1") (pintype "passive"))
      (node (ref "R101") (pin "2") (pinfunction "2_2") (pintype "passive"))
    )
    (net (code "33") (name "/BOOT PTA6") (class "Default")
      (node (ref "BOOT") (pin "6") (pinfunction "PTA6_6") (pintype "passive"))
      (node (ref "MCU") (pin "51") (pinfunction "PTA1_51") (pintype "input"))
    )
    (net (code "34") (name "/BOOT PTB1") (class "Default")
      (node (ref "BOOT") (pin "9") (pinfunction "PTB1/IRQ_6_9") (pintype "passive"))
      (node (ref "MCU") (pin "52") (pinfunction "PTA2_52") (pintype "input"))
    )
    (net (code "35") (name "/BPS CSN") (class "Default")
      (node (ref "BPS") (pin "4") (pinfunction "CSB_4") (pintype "input"))
      (node (ref "BPS") (pin "5") (pinfunction "CSB_5") (pintype "input"))
      (node (ref "MCU") (pin "141") (pinfunction "PTD12_141") (pintype "input"))
      (node (ref "R402") (pin "2") (pinfunction "2_2") (pintype "passive"))
    )
    (net (code "36") (name "/BUZZ") (class "Default")
      (node (ref "MCU") (pin "98") (pinfunction "PTB19_98") (pintype "input"))
      (node (ref "Q10") (pin "1") (pinfunction "G_1") (pintype "passive"))
      (node (ref "R602") (pin "2") (pinfunction "2_2") (pintype "passive"))
    )
    (net (code "37") (name "/CAN2RX") (class "Default")
      (node (ref "CAN2 TRAN") (pin "4") (pinfunction "R_4") (pintype "output"))
      (node (ref "MCU") (pin "65") (pinfunction "PTA13/LLWU_P4_65") (pintype "input"))
    )
    (net (code "38") (name "/CAN2TX") (class "Default")
      (node (ref "CAN2 TRAN") (pin "1") (pinfunction "D_1") (pintype "input"))
      (node (ref "MCU") (pin "64") (pinfunction "PTA12_64") (pintype "input"))
    )
    (net (code "39") (name "/CAN2_N") (class "Default")
      (node (ref "CAN2 TRAN") (pin "6") (pinfunction "CANL_6") (pintype "bidirectional"))
      (node (ref "Primary Connector") (pin "46") (pinfunction "46_46") (pintype "passive"))
      (node (ref "R308") (pin "2") (pinfunction "2_2") (pintype "passive"))
    )
    (net (code "40") (name "/CAN2_P") (class "Default")
      (node (ref "CAN2 TRAN") (pin "7") (pinfunction "CANH_7") (pintype "bidirectional"))
      (node (ref "Primary Connector") (pin "21") (pinfunction "21_21") (pintype "passive"))
      (node (ref "R308") (pin "1") (pinfunction "1_1") (pintype "passive"))
    )
    (net (code "41") (name "/CANF CLKO") (class "Default")
      (node (ref "MCU") (pin "75") (pinfunction "PTA24_75") (pintype "input"))
    )
    (net (code "42") (name "/CANF CS") (class "Default")
      (node (ref "MCU") (pin "68") (pinfunction "PTA16_68") (pintype "input"))
    )
    (net (code "43") (name "/CANF INTN") (class "Default")
      (node (ref "MCU") (pin "76") (pinfunction "PTA25_76") (pintype "input"))
    )
    (net (code "44") (name "/CANF INTN0") (class "Default")
      (node (ref "MCU") (pin "67") (pinfunction "PTA15_67") (pintype "input"))
    )
    (net (code "45") (name "/CANF INTN1") (class "Default")
      (node (ref "MCU") (pin "55") (pinfunction "PTA5_55") (pintype "input"))
    )
    (net (code "46") (name "/CANF_N") (class "Default")
      (node (ref "Primary Connector") (pin "47") (pinfunction "47_47") (pintype "passive"))
    )
    (net (code "47") (name "/CANF_P") (class "Default")
      (node (ref "Primary Connector") (pin "22") (pinfunction "22_22") (pintype "passive"))
    )
    (net (code "48") (name "/DC") (class "Default")
      (node (ref "BOOT") (pin "8") (pinfunction "PTB0/IRQ_5_8") (pintype "passive"))
      (node (ref "Boot J") (pin "4") (pinfunction "4_4") (pintype "passive"))
      (node (ref "MCU") (pin "50") (pinfunction "PTA0_50") (pintype "input"))
    )
    (net (code "49") (name "/DD") (class "Default")
      (node (ref "BOOT") (pin "7") (pinfunction "PTA7/IRQ_4_7") (pintype "passive"))
      (node (ref "Boot J") (pin "2") (pinfunction "2_2") (pintype "passive"))
      (node (ref "MCU") (pin "53") (pinfunction "PTA3_53") (pintype "input"))
    )
    (net (code "50") (name "/DE") (class "Default")
      (node (ref "BOOT") (pin "3") (pinfunction "PTA3_3") (pintype "passive"))
      (node (ref "Boot J") (pin "6") (pinfunction "6_6") (pintype "passive"))
    )
    (net (code "51") (name "/DIO1") (class "Default")
      (node (ref "MCU") (pin "48") (pinfunction "PTE27_48") (pintype "input"))
      (node (ref "Secondary Connector") (pin "26") (pinfunction "26_26") (pintype "passive"))
    )
    (net (code "52") (name "/DIO2") (class "Default")
      (node (ref "MCU") (pin "49") (pinfunction "PTE28_49") (pintype "input"))
      (node (ref "Secondary Connector") (pin "13") (pinfunction "13_13") (pintype "passive"))
    )
    (net (code "54") (name "/EX AIN1") (class "Default")
      (node (ref "Secondary Connector") (pin "1") (pinfunction "1_1") (pintype "passive"))
    )
    (net (code "55") (name "/EX AIN2") (class "Default")
      (node (ref "Secondary Connector") (pin "3") (pinfunction "3_3") (pintype "passive"))
    )
    (net (code "56") (name "/EX AIN3") (class "Default")
      (node (ref "Secondary Connector") (pin "4") (pinfunction "4_4") (pintype "passive"))
    )
    (net (code "57") (name "/EX AIN4") (class "Default")
      (node (ref "Secondary Connector") (pin "6") (pinfunction "6_6") (pintype "passive"))
    )
    (net (code "58") (name "/EX AIN5") (class "Default")
      (node (ref "Secondary Connector") (pin "7") (pinfunction "7_7") (pintype "passive"))
    )
    (net (code "59") (name "/EX AIN6") (class "Default")
      (node (ref "Secondary Connector") (pin "9") (pinfunction "9_9") (pintype "passive"))
    )
    (net (code "60") (name "/EX AIN7") (class "Default")
      (node (ref "Secondary Connector") (pin "10") (pinfunction "10_10") (pintype "passive"))
    )
    (net (code "61") (name "/EX AIN8") (class "Default")
      (node (ref "Secondary Connector") (pin "12") (pinfunction "12_12") (pintype "passive"))
    )
    (net (code "62") (name "/EXTAL32") (class "Default")
      (node (ref "MCU") (pin "41") (pinfunction "EXTAL32_41") (pintype "input"))
      (node (ref "Y2") (pin "2") (pinfunction "Out/In_2") (pintype "passive"))
    )
    (net (code "63") (name "/GPS INT") (class "Default")
      (node (ref "FB8") (pin "2") (pinfunction "2_2") (pintype "passive"))
      (node (ref "MCU") (pin "13") (pinfunction "PTE10/LLWU_P18_13") (pintype "input"))
    )
    (net (code "64") (name "/GPS RST") (class "Default")
      (node (ref "FB5") (pin "1") (pinfunction "1_1") (pintype "passive"))
      (node (ref "MCU") (pin "14") (pinfunction "PTE11_14") (pintype "input"))
    )
    (net (code "65") (name "/GPS TP") (class "Default")
      (node (ref "FB9") (pin "2") (pinfunction "2_2") (pintype "passive"))
      (node (ref "R401") (pin "1") (pinfunction "1_1") (pintype "passive"))
    )
    (net (code "67") (name "/HPO BAT+1") (class "Default")
      (node (ref "Primary Connector") (pin "2") (pinfunction "2_2") (pintype "passive"))
      (node (ref "Primary Connector") (pin "27") (pinfunction "27_27") (pintype "passive"))
      (node (ref "Primary Connector") (pin "29") (pinfunction "29_29") (pintype "passive"))
      (node (ref "Primary Connector") (pin "4") (pinfunction "4_4") (pintype "passive"))
    )
    (net (code "68") (name "/HPO BAT+2") (class "Default")
      (node (ref "Primary Connector") (pin "31") (pinfunction "31_31") (pintype "passive"))
      (node (ref "Primary Connector") (pin "33") (pinfunction "33_33") (pintype "passive"))
      (node (ref "Primary Connector") (pin "6") (pinfunction "6_6") (pintype "passive"))
      (node (ref "Primary Connector") (pin "8") (pinfunction "8_8") (pintype "passive"))
    )
    (net (code "69") (name "/HPO BAT+3") (class "Default")
      (node (ref "Primary Connector") (pin "10") (pinfunction "10_10") (pintype "passive"))
      (node (ref "Primary Connector") (pin "12") (pinfunction "12_12") (pintype "passive"))
      (node (ref "Primary Connector") (pin "35") (pinfunction "35_35") (pintype "passive"))
      (node (ref "Primary Connector") (pin "37") (pinfunction "37_37") (pintype "passive"))
    )
    (net (code "70") (name "/HPO BAT+4") (class "Default")
      (node (ref "Primary Connector") (pin "14") (pinfunction "14_14") (pintype "passive"))
      (node (ref "Primary Connector") (pin "16") (pinfunction "16_16") (pintype "passive"))
      (node (ref "Primary Connector") (pin "39") (pinfunction "39_39") (pintype "passive"))
      (node (ref "Primary Connector") (pin "41") (pinfunction "41_41") (pintype "passive"))
    )
    (net (code "71") (name "/HPO BAT+5") (class "Default")
      (node (ref "Primary Connector") (pin "18") (pinfunction "18_18") (pintype "passive"))
      (node (ref "Primary Connector") (pin "20") (pinfunction "20_20") (pintype "passive"))
      (node (ref "Primary Connector") (pin "43") (pinfunction "43_43") (pintype "passive"))
      (node (ref "Primary Connector") (pin "45") (pinfunction "45_45") (pintype "passive"))
    )
    (net (code "73") (name "/HPO D1") (class "Default")
      (node (ref "Primary Connector") (pin "1") (pinfunction "1_1") (pintype "passive"))
      (node (ref "Primary Connector") (pin "26") (pinfunction "26_26") (pintype "passive"))
    )
    (net (code "74") (name "/HPO D2") (class "Default")
      (node (ref "Primary Connector") (pin "28") (pinfunction "28_28") (pintype "passive"))
      (node (ref "Primary Connector") (pin "3") (pinfunction "3_3") (pintype "passive"))
    )
    (net (code "75") (name "/HPO D3") (class "Default")
      (node (ref "Primary Connector") (pin "30") (pinfunction "30_30") (pintype "passive"))
      (node (ref "Primary Connector") (pin "5") (pinfunction "5_5") (pintype "passive"))
    )
    (net (code "76") (name "/HPO D4") (class "Default")
      (node (ref "Primary Connector") (pin "32") (pinfunction "32_32") (pintype "passive"))
      (node (ref "Primary Connector") (pin "7") (pinfunction "7_7") (pintype "passive"))
    )
    (net (code "77") (name "/HPO D5") (class "Default")
      (node (ref "Primary Connector") (pin "34") (pinfunction "34_34") (pintype "passive"))
      (node (ref "Primary Connector") (pin "9") (pinfunction "9_9") (pintype "passive"))
    )
    (net (code "78") (name "/HPO D6") (class "Default")
      (node (ref "Primary Connector") (pin "11") (pinfunction "11_11") (pintype "passive"))
      (node (ref "Primary Connector") (pin "36") (pinfunction "36_36") (pintype "passive"))
    )
    (net (code "79") (name "/HPO D7") (class "Default")
      (node (ref "Primary Connector") (pin "13") (pinfunction "13_13") (pintype "passive"))
      (node (ref "Primary Connector") (pin "38") (pinfunction "38_38") (pintype "passive"))
    )
    (net (code "80") (name "/HPO D8") (class "Default")
      (node (ref "Primary Connector") (pin "15") (pinfunction "15_15") (pintype "passive"))
      (node (ref "Primary Connector") (pin "40") (pinfunction "40_40") (pintype "passive"))
    )
    (net (code "81") (name "/HPO D9") (class "Default")
      (node (ref "Primary Connector") (pin "17") (pinfunction "17_17") (pintype "passive"))
      (node (ref "Primary Connector") (pin "42") (pinfunction "42_42") (pintype "passive"))
    )
    (net (code "82") (name "/HPO D10") (class "Default")
      (node (ref "Primary Connector") (pin "19") (pinfunction "19_19") (pintype "passive"))
      (node (ref "Primary Connector") (pin "44") (pinfunction "44_44") (pintype "passive"))
    )
    (net (code "84") (name "/HPO DIG1") (class "Default")
      (node (ref "MCU") (pin "139") (pinfunction "PTD10_139") (pintype "input"))
    )
    (net (code "85") (name "/HPO DIG2") (class "Default")
      (node (ref "MCU") (pin "126") (pinfunction "PTC19_126") (pintype "input"))
    )
    (net (code "86") (name "/HPO DIG3") (class "Default")
      (node (ref "MCU") (pin "125") (pinfunction "PTC18_125") (pintype "input"))
    )
    (net (code "87") (name "/HPO DIG4") (class "Default")
      (node (ref "MCU") (pin "124") (pinfunction "PTC17_124") (pintype "input"))
    )
    (net (code "88") (name "/HPO DIG5") (class "Default")
      (node (ref "MCU") (pin "123") (pinfunction "PTC16_123") (pintype "input"))
    )
    (net (code "89") (name "/HPO DIG6") (class "Default")
      (node (ref "MCU") (pin "120") (pinfunction "PTC15_120") (pintype "input"))
    )
    (net (code "90") (name "/HPO DIG7") (class "Default")
      (node (ref "MCU") (pin "119") (pinfunction "PTC14_119") (pintype "input"))
    )
    (net (code "91") (name "/HPO DIG8") (class "Default")
      (node (ref "MCU") (pin "118") (pinfunction "PTC13_118") (pintype "input"))
    )
    (net (code "92") (name "/HPO DIG9") (class "Default")
      (node (ref "MCU") (pin "117") (pinfunction "PTC12_117") (pintype "input"))
    )
    (net (code "93") (name "/HPO DIG10") (class "Default")
      (node (ref "MCU") (pin "90") (pinfunction "PTB9_90") (pintype "input"))
    )
    (net (code "95") (name "/HPO PWM1") (class "Default")
      (node (ref "MCU") (pin "136") (pinfunction "PTD7_136") (pintype "input"))
    )
    (net (code "96") (name "/HPO PWM2") (class "Default")
      (node (ref "MCU") (pin "131") (pinfunction "PTD4/LLWU_P14_131") (pintype "input"))
    )
    (net (code "97") (name "/HPO PWM3") (class "Default")
      (node (ref "MCU") (pin "130") (pinfunction "PTD3_130") (pintype "input"))
    )
    (net (code "98") (name "/HPO PWM4") (class "Default")
      (node (ref "MCU") (pin "129") (pinfunction "PTD2/LLWU_P13_129") (pintype "input"))
    )
    (net (code "99") (name "/HPO PWM5") (class "Default")
      (node (ref "MCU") (pin "127") (pinfunction "PTD0/LLWU_P12_127") (pintype "input"))
    )
    (net (code "100") (name "/HPO PWM6") (class "Default")
      (node (ref "MCU") (pin "113") (pinfunction "PTC8_113") (pintype "input"))
    )
    (net (code "101") (name "/HPO PWM7") (class "Default")
      (node (ref "MCU") (pin "109") (pinfunction "PTC4/LLWU_P8_109") (pintype "input"))
    )
    (net (code "102") (name "/HPO PWM8") (class "Default")
      (node (ref "MCU") (pin "106") (pinfunction "PTC3/LLWU_P7_106") (pintype "input"))
    )
    (net (code "103") (name "/HPO PWM9") (class "Default")
      (node (ref "MCU") (pin "105") (pinfunction "PTC2_105") (pintype "input"))
    )
    (net (code "104") (name "/HPO PWM10") (class "Default")
      (node (ref "MCU") (pin "104") (pinfunction "PTC1/LLWU_P6_104") (pintype "input"))
    )
    (net (code "106") (name "/HPO VD1") (class "Default")
      (node (ref "MCU") (pin "133") (pinfunction "PTD6/LLWU_P15_133") (pintype "input"))
    )
    (net (code "107") (name "/HPO VD2") (class "Default")
      (node (ref "MCU") (pin "132") (pinfunction "PTD5_132") (pintype "input"))
    )
    (net (code "108") (name "/HPO VD3") (class "Default")
      (node (ref "MCU") (pin "128") (pinfunction "PTD1_128") (pintype "input"))
    )
    (net (code "109") (name "/HPO VD4") (class "Default")
      (node (ref "MCU") (pin "116") (pinfunction "PTC11/LLWU_P11_116") (pintype "input"))
    )
    (net (code "110") (name "/HPO VD5") (class "Default")
      (node (ref "MCU") (pin "115") (pinfunction "PTC10_115") (pintype "input"))
    )
    (net (code "111") (name "/HPO VD6") (class "Default")
      (node (ref "MCU") (pin "114") (pinfunction "PTC9_114") (pintype "input"))
    )
    (net (code "112") (name "/HPO VD7") (class "Default")
      (node (ref "MCU") (pin "103") (pinfunction "PTC0_103") (pintype "input"))
    )
    (net (code "113") (name "/HPO VD8") (class "Default")
      (node (ref "MCU") (pin "92") (pinfunction "PTB11_92") (pintype "input"))
    )
    (net (code "114") (name "/HPO VD9") (class "Default")
      (node (ref "MCU") (pin "91") (pinfunction "PTB10_91") (pintype "input"))
    )
    (net (code "115") (name "/HPO VD10") (class "Default")
      (node (ref "MCU") (pin "86") (pinfunction "PTB5_86") (pintype "input"))
    )
    (net (code "116") (name "/IMU1 RST") (class "Default")
      (node (ref "IMU1") (pin "11") (pinfunction "~{RESET}_11") (pintype "input"))
      (node (ref "MCU") (pin "47") (pinfunction "PTE26_47") (pintype "input"))
      (node (ref "R405") (pin "2") (pinfunction "2_2") (pintype "passive"))
    )
    (net (code "117") (name "/IMU2 CSBA") (class "Default")
      (node (ref "IMU2") (pin "14") (pinfunction "CSB1_14") (pintype "input"))
      (node (ref "MCU") (pin "143") (pinfunction "PTD14_143") (pintype "input"))
      (node (ref "R408") (pin "2") (pinfunction "2_2") (pintype "passive"))
    )
    (net (code "118") (name "/IMU2 CSBG") (class "Default")
      (node (ref "IMU2") (pin "5") (pinfunction "CSB2_5") (pintype "input"))
      (node (ref "MCU") (pin "142") (pinfunction "PTD13_142") (pintype "input"))
      (node (ref "R407") (pin "2") (pinfunction "2_2") (pintype "passive"))
    )
    (net (code "119") (name "/LoRa CSN") (class "Default")
      (node (ref "LoRa SPI") (pin "1") (pinfunction "1_1") (pintype "passive"))
      (node (ref "MCU") (pin "77") (pinfunction "PTA26_77") (pintype "input"))
      (node (ref "R604") (pin "2") (pinfunction "2_2") (pintype "passive"))
    )
    (net (code "120") (name "/LoRa INT") (class "Default")
      (node (ref "LoRa Misc") (pin "1") (pinfunction "1_1") (pintype "passive"))
      (node (ref "MCU") (pin "79") (pinfunction "PTA28_79") (pintype "input"))
    )
    (net (code "121") (name "/LoRa RST") (class "Default")
      (node (ref "LoRa Misc") (pin "2") (pinfunction "2_2") (pintype "passive"))
      (node (ref "MCU") (pin "80") (pinfunction "PTA29_80") (pintype "input"))
    )
    (net (code "122") (name "/MISO") (class "Default")
      (node (ref "ACC") (pin "1") (pinfunction "SDO/ADDR_1") (pintype "bidirectional"))
      (node (ref "BPS") (pin "6") (pinfunction "SDO_6") (pintype "output"))
      (node (ref "IMU2") (pin "10") (pinfunction "SDO2_10") (pintype "output"))
      (node (ref "IMU2") (pin "15") (pinfunction "SDO1_15") (pintype "output"))
      (node (ref "LoRa SPI") (pin "2") (pinfunction "2_2") (pintype "passive"))
      (node (ref "MCU") (pin "112") (pinfunction "PTC7_112") (pintype "input"))
      (node (ref "NRF SPI") (pin "2") (pinfunction "2_2") (pintype "passive"))
    )
    (net (code "123") (name "/MOSI") (class "Default")
      (node (ref "ACC") (pin "2") (pinfunction "SDI/SDA_2") (pintype "input"))
      (node (ref "BPS") (pin "7") (pinfunction "SDI/SDA_7") (pintype "bidirectional"))
      (node (ref "IMU2") (pin "9") (pinfunction "SDx_9") (pintype "input"))
      (node (ref "LoRa SPI") (pin "3") (pinfunction "3_3") (pintype "passive"))
      (node (ref "MCU") (pin "111") (pinfunction "PTC6/LLWU_P10_111") (pintype "input"))
      (node (ref "NRF SPI") (pin "3") (pinfunction "3_3") (pintype "passive"))
    )
    (net (code "125") (name "/MUX B1") (class "Default")
      (node (ref "MUX") (pin "4") (pinfunction "B1_4") (pintype "passive"))
    )
    (net (code "126") (name "/MUX B2") (class "Default")
      (node (ref "MUX") (pin "3") (pinfunction "B2_3") (pintype "passive"))
    )
    (net (code "127") (name "/MUX B3") (class "Default")
      (node (ref "MUX") (pin "2") (pinfunction "B3_2") (pintype "passive"))
    )
    (net (code "128") (name "/MUX B4") (class "Default")
      (node (ref "MUX") (pin "1") (pinfunction "B4_1") (pintype "passive"))
    )
    (net (code "129") (name "/MUX B5") (class "Default")
      (node (ref "MUX") (pin "15") (pinfunction "B5_15") (pintype "passive"))
    )
    (net (code "130") (name "/MUX B6") (class "Default")
      (node (ref "MUX") (pin "14") (pinfunction "B6_14") (pintype "passive"))
    )
    (net (code "131") (name "/MUX B7") (class "Default")
      (node (ref "MUX") (pin "13") (pinfunction "B7_13") (pintype "passive"))
    )
    (net (code "132") (name "/MUX B8") (class "Default")
      (node (ref "MUX") (pin "12") (pinfunction "B8_12") (pintype "passive"))
    )
    (net (code "133") (name "/MUX OEN") (class "Default")
      (node (ref "MCU") (pin "102") (pinfunction "PTB23_102") (pintype "input"))
      (node (ref "MUX") (pin "7") (pinfunction "~{OE}_7") (pintype "passive"))
      (node (ref "R501") (pin "2") (pinfunction "2_2") (pintype "passive"))
    )
    (net (code "134") (name "/MUX S0") (class "Default")
      (node (ref "MCU") (pin "99") (pinfunction "PTB20_99") (pintype "input"))
      (node (ref "MUX") (pin "11") (pinfunction "S0_11") (pintype "passive"))
    )
    (net (code "135") (name "/MUX S1") (class "Default")
      (node (ref "MCU") (pin "100") (pinfunction "PTB21_100") (pintype "input"))
      (node (ref "MUX") (pin "10") (pinfunction "S1_10") (pintype "passive"))
    )
    (net (code "136") (name "/MUX S2") (class "Default")
      (node (ref "MCU") (pin "101") (pinfunction "PTB22_101") (pintype "input"))
      (node (ref "MUX") (pin "9") (pinfunction "S2_9") (pintype "passive"))
    )
    (net (code "137") (name "/NRF CE") (class "Default")
      (node (ref "MCU") (pin "144") (pinfunction "PTD15_144") (pintype "input"))
      (node (ref "NRF Misc") (pin "2") (pinfunction "2_2") (pintype "passive"))
    )
    (net (code "138") (name "/NRF CSN") (class "Default")
      (node (ref "MCU") (pin "140") (pinfunction "PTD11/LLWU_P25_140") (pintype "input"))
      (node (ref "NRF SPI") (pin "1") (pinfunction "1_1") (pintype "passive"))
      (node (ref "R603") (pin "2") (pinfunction "2_2") (pintype "passive"))
    )
    (net (code "139") (name "/NRF IRQ") (class "Default")
      (node (ref "MCU") (pin "66") (pinfunction "PTA14_66") (pintype "input"))
      (node (ref "NRF Misc") (pin "1") (pinfunction "1_1") (pintype "passive"))
    )
    (net (code "145") (name "/Out BLU1") (class "Default")
      (node (ref "PWM DRIVER") (pin "11") (pinfunction "LED5_11") (pintype "tri_state"))
    )
    (net (code "146") (name "/Out BLU2") (class "Default")
      (node (ref "PWM DRIVER") (pin "8") (pinfunction "LED2_8") (pintype "tri_state"))
    )
    (net (code "148") (name "/Out GRN1") (class "Default")
      (node (ref "PWM DRIVER") (pin "10") (pinfunction "LED4_10") (pintype "tri_state"))
    )
    (net (code "149") (name "/Out GRN2") (class "Default")
      (node (ref "PWM DRIVER") (pin "7") (pinfunction "LED1_7") (pintype "tri_state"))
    )
    (net (code "151") (name "/Out RED1") (class "Default")
      (node (ref "PWM DRIVER") (pin "9") (pinfunction "LED3_9") (pintype "tri_state"))
    )
    (net (code "152") (name "/Out RED2") (class "Default")
      (node (ref "PWM DRIVER") (pin "6") (pinfunction "LED0_6") (pintype "tri_state"))
    )
    (net (code "153") (name "/PCA OEN") (class "Default")
      (node (ref "MCU") (pin "54") (pinfunction "PTA4/LLWU_P3_54") (pintype "input"))
      (node (ref "PWM DRIVER") (pin "23") (pinfunction "~{OE}_23") (pintype "input"))
      (node (ref "R503") (pin "2") (pinfunction "2_2") (pintype "passive"))
    )
    (net (code "154") (name "/Prog") (class "Default")
      (node (ref "BOOT") (pin "10") (pinfunction "PTB2/IRQ_7_10") (pintype "passive"))
      (node (ref "Boot J") (pin "3") (pinfunction "3_3") (pintype "passive"))
    )
    (net (code "155") (name "/RS485 D") (class "Default")
      (node (ref "MCU") (pin "96") (pinfunction "PTB17_96") (pintype "input"))
      (node (ref "RS-485") (pin "3") (pinfunction "D_3") (pintype "passive"))
    )
    (net (code "156") (name "/RS485 R") (class "Default")
      (node (ref "MCU") (pin "95") (pinfunction "PTB16_95") (pintype "input"))
      (node (ref "RS-485") (pin "2") (pinfunction "R_2") (pintype "passive"))
    )
    (net (code "157") (name "/RS485_RX_N") (class "Default")
      (node (ref "Primary Connector") (pin "50") (pinfunction "50_50") (pintype "passive"))
      (node (ref "R305") (pin "1") (pinfunction "1_1") (pintype "passive"))
      (node (ref "RS-485") (pin "7") (pinfunction "B_7") (pintype "passive"))
    )
    (net (code "158") (name "/RS485_RX_P") (class "Default")
      (node (ref "Primary Connector") (pin "25") (pinfunction "25_25") (pintype "passive"))
      (node (ref "R305") (pin "2") (pinfunction "2_2") (pintype "passive"))
      (node (ref "RS-485") (pin "8") (pinfunction "A_8") (pintype "passive"))
    )
    (net (code "159") (name "/RS485_TX_N") (class "Default")
      (node (ref "Primary Connector") (pin "49") (pinfunction "49_49") (pintype "passive"))
      (node (ref "R306") (pin "2") (pinfunction "2_2") (pintype "passive"))
      (node (ref "RS-485") (pin "5") (pinfunction "Y_5") (pintype "passive"))
    )
    (net (code "160") (name "/RS485_TX_P") (class "Default")
      (node (ref "Primary Connector") (pin "24") (pinfunction "24_24") (pintype "passive"))
      (node (ref "R306") (pin "1") (pinfunction "1_1") (pintype "passive"))
      (node (ref "RS-485") (pin "6") (pinfunction "Z_6") (pintype "passive"))
    )
    (net (code "161") (name "/Reset") (class "Default")
      (node (ref "BOOT") (pin "13") (pinfunction "PTB5/IRQ_12_13") (pintype "passive"))
      (node (ref "BOOT") (pin "4") (pinfunction "PTA4_4") (pintype "passive"))
      (node (ref "Boot J") (pin "1") (pinfunction "1_1") (pintype "passive"))
      (node (ref "MCU") (pin "74") (pinfunction "RESET_b_74") (pintype "input"))
    )
    (net (code "162") (name "/SCL") (class "Default")
      (node (ref "FB6") (pin "1") (pinfunction "1_1") (pintype "passive"))
      (node (ref "IMU1") (pin "19") (pinfunction "COM1_19") (pintype "bidirectional"))
      (node (ref "MCU") (pin "83") (pinfunction "PTB2_83") (pintype "input"))
      (node (ref "PWM DRIVER") (pin "26") (pinfunction "SCL_26") (pintype "input"))
      (node (ref "R303") (pin "2") (pinfunction "2_2") (pintype "passive"))
    )
    (net (code "163") (name "/SCLK") (class "Default")
      (node (ref "ACC") (pin "12") (pinfunction "SCLK/SCL_12") (pintype "input"))
      (node (ref "BPS") (pin "8") (pinfunction "SCLK_8") (pintype "input"))
      (node (ref "IMU2") (pin "8") (pinfunction "SCx_8") (pintype "input"))
      (node (ref "LoRa SPI") (pin "4") (pinfunction "4_4") (pintype "passive"))
      (node (ref "MCU") (pin "110") (pinfunction "PTC5/LLWU_P9_110") (pintype "input"))
      (node (ref "NRF SPI") (pin "4") (pinfunction "4_4") (pintype "passive"))
    )
    (net (code "164") (name "/SD CLK") (class "Default")
      (node (ref "MCU") (pin "3") (pinfunction "PTE2/LLWU_P1_3") (pintype "input"))
      (node (ref "SD") (pin "5") (pinfunction "CLK_5") (pintype "passive"))
    )
    (net (code "165") (name "/SD CMD") (class "Default")
      (node (ref "MCU") (pin "4") (pinfunction "PTE3_4") (pintype "input"))
      (node (ref "SD") (pin "3") (pinfunction "VSS1_3") (pintype "passive"))
    )
    (net (code "166") (name "/SD DAT0") (class "Default")
      (node (ref "MCU") (pin "2") (pinfunction "PTE1/LLWU_P0_2") (pintype "input"))
      (node (ref "SD") (pin "7") (pinfunction "DAT0_7") (pintype "passive"))
    )
    (net (code "167") (name "/SD DAT1") (class "Default")
      (node (ref "MCU") (pin "1") (pinfunction "PTE0_1") (pintype "input"))
      (node (ref "SD") (pin "8") (pinfunction "DAT1_8") (pintype "passive"))
    )
    (net (code "168") (name "/SD DAT2") (class "Default")
      (node (ref "MCU") (pin "8") (pinfunction "PTE5_8") (pintype "input"))
      (node (ref "SD") (pin "1") (pinfunction "CD/DAT3_1") (pintype "passive"))
    )
    (net (code "169") (name "/SD DAT3") (class "Default")
      (node (ref "MCU") (pin "7") (pinfunction "PTE4/LLWU_P2_7") (pintype "input"))
      (node (ref "SD") (pin "2") (pinfunction "CMD_2") (pintype "passive"))
    )
    (net (code "170") (name "/SDA") (class "Default")
      (node (ref "FB7") (pin "1") (pinfunction "1_1") (pintype "passive"))
      (node (ref "IMU1") (pin "20") (pinfunction "COM0_20") (pintype "bidirectional"))
      (node (ref "MCU") (pin "84") (pinfunction "PTB3_84") (pintype "input"))
      (node (ref "PWM DRIVER") (pin "27") (pinfunction "SDA_27") (pintype "bidirectional"))
      (node (ref "R304") (pin "1") (pinfunction "1_1") (pintype "passive"))
    )
    (net (code "171") (name "/USB D+") (class "Default")
      (node (ref "R302") (pin "2") (pinfunction "2_2") (pintype "passive"))
      (node (ref "USB") (pin "3") (pinfunction "D+_3") (pintype "passive"))
    )
    (net (code "172") (name "/USB D-") (class "Default")
      (node (ref "R301") (pin "2") (pinfunction "2_2") (pintype "passive"))
      (node (ref "USB") (pin "2") (pinfunction "D-_2") (pintype "passive"))
    )
    (net (code "173") (name "/USB0 DM") (class "Default")
      (node (ref "MCU") (pin "20") (pinfunction "USB0_DM_20") (pintype "input"))
      (node (ref "R301") (pin "1") (pinfunction "1_1") (pintype "passive"))
    )
    (net (code "174") (name "/USB0 DP") (class "Default")
      (node (ref "MCU") (pin "19") (pinfunction "USB0_DP_19") (pintype "input"))
      (node (ref "R302") (pin "1") (pinfunction "1_1") (pintype "passive"))
    )
    (net (code "175") (name "/USBV+") (class "Default")
      (node (ref "D2") (pin "2") (pinfunction "A_2") (pintype "passive"))
      (node (ref "USB") (pin "1") (pinfunction "VBUS_1") (pintype "passive"))
    )
    (net (code "176") (name "/VD 3.3V") (class "Default")
      (node (ref "MCU") (pin "85") (pinfunction "PTB4_85") (pintype "input"))
      (node (ref "R104") (pin "2") (pinfunction "2_2") (pintype "passive"))
      (node (ref "R105") (pin "1") (pinfunction "1_1") (pintype "passive"))
    )
    (net (code "177") (name "/VD 5V") (class "Default")
      (node (ref "MCU") (pin "69") (pinfunction "PTA17_69") (pintype "input"))
      (node (ref "R106") (pin "2") (pinfunction "2_2") (pintype "passive"))
      (node (ref "R107") (pin "1") (pinfunction "1_1") (pintype "passive"))
    )
    (net (code "178") (name "/VDDA") (class "Default")
      (node (ref "C207") (pin "2") (pinfunction "2_2") (pintype "passive"))
      (node (ref "FB2") (pin "1") (pinfunction "1_1") (pintype "passive"))
      (node (ref "MCU") (pin "31") (pinfunction "VDDA_31") (pintype "input"))
      (node (ref "R201") (pin "2") (pinfunction "2_2") (pintype "passive"))
    )
    (net (code "179") (name "/VREF OUT") (class "Default")
      (node (ref "C208") (pin "2") (pinfunction "2_2") (pintype "passive"))
      (node (ref "MCU") (pin "37") (pinfunction "VREF_OUT/CMP1_IN5/CMP0_IN5/ADC1_SE18_37") (pintype "input"))
    )
    (net (code "180") (name "/VREFH") (class "Default")
      (node (ref "C206") (pin "2") (pinfunction "2_2") (pintype "passive"))
      (node (ref "MCU") (pin "32") (pinfunction "VREFH_32") (pintype "input"))
      (node (ref "R201") (pin "1") (pinfunction "1_1") (pintype "passive"))
    )
    (net (code "181") (name "/VREFL") (class "Default")
      (node (ref "C206") (pin "1") (pinfunction "1_1") (pintype "passive"))
      (node (ref "C207") (pin "1") (pinfunction "1_1") (pintype "passive"))
      (node (ref "C208") (pin "1") (pinfunction "1_1") (pintype "passive"))
      (node (ref "FB3") (pin "2") (pinfunction "2_2") (pintype "passive"))
      (node (ref "MCU") (pin "33") (pinfunction "VREFL_33") (pintype "input"))
      (node (ref "MCU") (pin "34") (pinfunction "VSSA_34") (pintype "input"))
    )
    (net (code "182") (name "/XTAL32") (class "Default")
      (node (ref "MCU") (pin "40") (pinfunction "XTAL32_40") (pintype "input"))
      (node (ref "Y2") (pin "1") (pinfunction "In/Out_1") (pintype "passive"))
    )
    (net (code "183") (name "/Y1 A") (class "Default")
      (node (ref "MCU") (pin "72") (pinfunction "PTA18_72") (pintype "input"))
      (node (ref "Y1") (pin "1") (pinfunction "1_1") (pintype "passive"))
    )
    (net (code "184") (name "/Y1 B") (class "Default")
      (node (ref "MCU") (pin "73") (pinfunction "PTA19_73") (pintype "input"))
      (node (ref "Y1") (pin "3") (pinfunction "3_3") (pintype "passive"))
    )
    (net (code "185") (name "3.3V") (class "Default")
      (node (ref "3.3V") (pin "2") (pinfunction "OUTPUT_2") (pintype "passive"))
      (node (ref "3.3V") (pin "4") (pinfunction "VOUT_4") (pintype "passive"))
      (node (ref "ACC") (pin "3") (pinfunction "IO_VDD_3") (pintype "power_in"))
      (node (ref "ACC") (pin "7") (pinfunction "VDD_7") (pintype "power_in"))
      (node (ref "BOOT") (pin "1") (pinfunction "VDD_VREFH_1") (pintype "passive"))
      (node (ref "BPS") (pin "1") (pinfunction "VDD_1") (pintype "power_in"))
      (node (ref "BUZZER") (pin "2") (pinfunction "+POLARITY_2") (pintype "passive"))
      (node (ref "C104") (pin "2") (pinfunction "2_2") (pintype "passive"))
      (node (ref "C201") (pin "2") (pinfunction "2_2") (pintype "passive"))
      (node (ref "C202") (pin "2") (pinfunction "2_2") (pintype "passive"))
      (node (ref "C203") (pin "2") (pinfunction "2_2") (pintype "passive"))
      (node (ref "C204") (pin "2") (pinfunction "2_2") (pintype "passive"))
      (node (ref "C205") (pin "2") (pinfunction "2_2") (pintype "passive"))
      (node (ref "C209") (pin "2") (pinfunction "2_2") (pintype "passive"))
      (node (ref "C210") (pin "2") (pinfunction "2_2") (pintype "passive"))
      (node (ref "C302") (pin "2") (pinfunction "2_2") (pintype "passive"))
      (node (ref "C401") (pin "2") (pinfunction "2_2") (pintype "passive"))
      (node (ref "C402") (pin "2") (pinfunction "2_2") (pintype "passive"))
      (node (ref "C403") (pin "2") (pinfunction "2_2") (pintype "passive"))
      (node (ref "C404") (pin "2") (pinfunction "2_2") (pintype "passive"))
      (node (ref "C405") (pin "2") (pinfunction "2_2") (pintype "passive"))
      (node (ref "C407") (pin "2") (pinfunction "2_2") (pintype "passive"))
      (node (ref "C501") (pin "1") (pinfunction "1_1") (pintype "passive"))
      (node (ref "C502") (pin "1") (pinfunction "1_1") (pintype "passive"))
      (node (ref "C503") (pin "1") (pinfunction "1_1") (pintype "passive"))
      (node (ref "C601") (pin "2") (pinfunction "2_2") (pintype "passive"))
      (node (ref "C602") (pin "2") (pinfunction "2_2") (pintype "passive"))
      (node (ref "C603") (pin "2") (pinfunction "2_2") (pintype "passive"))
      (node (ref "CAN2 TRAN") (pin "3") (pinfunction "VCC_3") (pintype "power_in"))
      (node (ref "DEMUX") (pin "16") (pinfunction "VCC_16") (pintype "passive"))
      (node (ref "FB2") (pin "2") (pinfunction "2_2") (pintype "passive"))
      (node (ref "GPS") (pin "17") (pinfunction "VCC_17") (pintype "power_in"))
      (node (ref "GPS") (pin "2") (pinfunction "VCC_IO_2") (pintype "power_in"))
      (node (ref "GPS") (pin "3") (pinfunction "V_BCKP_3") (pintype "power_in"))
      (node (ref "IMU1") (pin "28") (pinfunction "VDDIO_28") (pintype "power_in"))
      (node (ref "IMU1") (pin "3") (pinfunction "VDD_3") (pintype "power_in"))
      (node (ref "IMU2") (pin "11") (pinfunction "VDDIO_11") (pintype "power_in"))
      (node (ref "IMU2") (pin "3") (pinfunction "VDD_3") (pintype "power_in"))
      (node (ref "LoRa Misc") (pin "4") (pinfunction "4_4") (pintype "passive"))
      (node (ref "MCU") (pin "108") (pinfunction "VDD_108") (pintype "input"))
      (node (ref "MCU") (pin "122") (pinfunction "VDD_122") (pintype "input"))
      (node (ref "MCU") (pin "135") (pinfunction "VDD_135") (pintype "input"))
      (node (ref "MCU") (pin "16") (pinfunction "VDD_16") (pintype "input"))
      (node (ref "MCU") (pin "21") (pinfunction "VREG_OUT_21") (pintype "input"))
      (node (ref "MCU") (pin "42") (pinfunction "VBAT_42") (pintype "input"))
      (node (ref "MCU") (pin "43") (pinfunction "VDD_43") (pintype "input"))
      (node (ref "MCU") (pin "5") (pinfunction "VDD_5") (pintype "input"))
      (node (ref "MCU") (pin "56") (pinfunction "VDD_56") (pintype "input"))
      (node (ref "MCU") (pin "70") (pinfunction "VDD_70") (pintype "input"))
      (node (ref "MCU") (pin "94") (pinfunction "VDD_94") (pintype "input"))
      (node (ref "MUX") (pin "16") (pinfunction "VCC_16") (pintype "passive"))
      (node (ref "NRF Misc") (pin "4") (pinfunction "4_4") (pintype "passive"))
      (node (ref "PWM DRIVER") (pin "28") (pinfunction "VDD_28") (pintype "power_in"))
      (node (ref "R102") (pin "2") (pinfunction "2_2") (pintype "passive"))
      (node (ref "R104") (pin "1") (pinfunction "1_1") (pintype "passive"))
      (node (ref "R303") (pin "1") (pinfunction "1_1") (pintype "passive"))
      (node (ref "R304") (pin "2") (pinfunction "2_2") (pintype "passive"))
      (node (ref "R402") (pin "1") (pinfunction "1_1") (pintype "passive"))
      (node (ref "R403") (pin "1") (pinfunction "1_1") (pintype "passive"))
      (node (ref "R405") (pin "1") (pinfunction "1_1") (pintype "passive"))
      (node (ref "R406") (pin "2") (pinfunction "2_2") (pintype "passive"))
      (node (ref "R407") (pin "1") (pinfunction "1_1") (pintype "passive"))
      (node (ref "R408") (pin "1") (pinfunction "1_1") (pintype "passive"))
      (node (ref "R501") (pin "1") (pinfunction "1_1") (pintype "passive"))
      (node (ref "R603") (pin "1") (pinfunction "1_1") (pintype "passive"))
      (node (ref "R604") (pin "1") (pinfunction "1_1") (pintype "passive"))
      (node (ref "SD") (pin "4") (pinfunction "VDD_4") (pintype "passive"))
    )
    (net (code "186") (name "5V") (class "Default")
      (node (ref "5V") (pin "3") (pinfunction "OUTPUT_3") (pintype "passive"))
      (node (ref "C106") (pin "2") (pinfunction "2_2") (pintype "passive"))
      (node (ref "C301") (pin "2") (pinfunction "2_2") (pintype "passive"))
      (node (ref "C604") (pin "2") (pinfunction "2_2") (pintype "passive"))
      (node (ref "R103") (pin "2") (pinfunction "2_2") (pintype "passive"))
      (node (ref "R106") (pin "1") (pinfunction "1_1") (pintype "passive"))
      (node (ref "RS-485") (pin "1") (pinfunction "VCC_1") (pintype "passive"))
      (node (ref "Secondary Connector") (pin "14") (pinfunction "14_14") (pintype "passive"))
      (node (ref "Secondary Connector") (pin "16") (pinfunction "16_16") (pintype "passive"))
      (node (ref "Secondary Connector") (pin "17") (pinfunction "17_17") (pintype "passive"))
      (node (ref "Secondary Connector") (pin "19") (pinfunction "19_19") (pintype "passive"))
      (node (ref "Secondary Connector") (pin "20") (pinfunction "20_20") (pintype "passive"))
      (node (ref "Secondary Connector") (pin "22") (pinfunction "22_22") (pintype "passive"))
      (node (ref "Secondary Connector") (pin "23") (pinfunction "23_23") (pintype "passive"))
      (node (ref "Secondary Connector") (pin "25") (pinfunction "25_25") (pintype "passive"))
    )
    (net (code "187") (name "GND") (class "Default")
      (node (ref "3.3V") (pin "1") (pinfunction "ADJ/GND_1") (pintype "passive"))
      (node (ref "5V") (pin "2") (pinfunction "ADJ/GND_1_2") (pintype "passive"))
      (node (ref "5V") (pin "4") (pinfunction "ADJ/GND_2_4") (pintype "passive"))
      (node (ref "ACC") (pin "8") (pinfunction "GND_8") (pintype "power_in"))
      (node (ref "ACC") (pin "9") (pinfunction "GND_9") (pintype "power_in"))
      (node (ref "BOOT") (pin "17") (pinfunction "EP_17") (pintype "passive"))
      (node (ref "BOOT") (pin "2") (pinfunction "VREFL_VSS_2") (pintype "passive"))
      (node (ref "BPS") (pin "2") (pinfunction "PS_2") (pintype "input"))
      (node (ref "BPS") (pin "3") (pinfunction "GND_3") (pintype "power_in"))
      (node (ref "BUCK") (pin "2") (pinfunction "GROUND_2") (pintype "passive"))
      (node (ref "Boot J") (pin "5") (pinfunction "5_5") (pintype "passive"))
      (node (ref "C101") (pin "2") (pinfunction "-_2") (pintype "passive"))
      (node (ref "C102") (pin "1") (pinfunction "1_1") (pintype "passive"))
      (node (ref "C103") (pin "1") (pinfunction "1_1") (pintype "passive"))
      (node (ref "C104") (pin "1") (pinfunction "1_1") (pintype "passive"))
      (node (ref "C105") (pin "1") (pinfunction "1_1") (pintype "passive"))
      (node (ref "C106") (pin "1") (pinfunction "1_1") (pintype "passive"))
      (node (ref "C201") (pin "1") (pinfunction "1_1") (pintype "passive"))
      (node (ref "C202") (pin "1") (pinfunction "1_1") (pintype "passive"))
      (node (ref "C203") (pin "1") (pinfunction "1_1") (pintype "passive"))
      (node (ref "C204") (pin "1") (pinfunction "1_1") (pintype "passive"))
      (node (ref "C205") (pin "1") (pinfunction "1_1") (pintype "passive"))
      (node (ref "C209") (pin "1") (pinfunction "1_1") (pintype "passive"))
      (node (ref "C210") (pin "1") (pinfunction "1_1") (pintype "passive"))
      (node (ref "C301") (pin "1") (pinfunction "1_1") (pintype "passive"))
      (node (ref "C302") (pin "1") (pinfunction "1_1") (pintype "passive"))
      (node (ref "C401") (pin "1") (pinfunction "1_1") (pintype "passive"))
      (node (ref "C402") (pin "1") (pinfunction "1_1") (pintype "passive"))
      (node (ref "C403") (pin "1") (pinfunction "1_1") (pintype "passive"))
      (node (ref "C404") (pin "1") (pinfunction "1_1") (pintype "passive"))
      (node (ref "C405") (pin "1") (pinfunction "1_1") (pintype "passive"))
      (node (ref "C406") (pin "1") (pinfunction "1_1") (pintype "passive"))
      (node (ref "C407") (pin "1") (pinfunction "1_1") (pintype "passive"))
      (node (ref "C501") (pin "2") (pinfunction "2_2") (pintype "passive"))
      (node (ref "C502") (pin "2") (pinfunction "2_2") (pintype "passive"))
      (node (ref "C503") (pin "2") (pinfunction "2_2") (pintype "passive"))
      (node (ref "C601") (pin "1") (pinfunction "1_1") (pintype "passive"))
      (node (ref "C602") (pin "1") (pinfunction "1_1") (pintype "passive"))
      (node (ref "C603") (pin "1") (pinfunction "1_1") (pintype "passive"))
      (node (ref "C604") (pin "1") (pinfunction "1_1") (pintype "passive"))
      (node (ref "CAN2 TRAN") (pin "2") (pinfunction "GND_2") (pintype "power_in"))
      (node (ref "DEMUX") (pin "17") (pinfunction "EP_17") (pintype "passive"))
      (node (ref "DEMUX") (pin "8") (pinfunction "GND_8") (pintype "passive"))
      (node (ref "DS1") (pin "1") (pinfunction "K_1") (pintype "passive"))
      (node (ref "DS2") (pin "1") (pinfunction "K_1") (pintype "passive"))
      (node (ref "DS3") (pin "1") (pinfunction "K_1") (pintype "passive"))
      (node (ref "DS4") (pin "1") (pinfunction "K_1") (pintype "passive"))
      (node (ref "FB3") (pin "1") (pinfunction "1_1") (pintype "passive"))
      (node (ref "GPS") (pin "1") (pinfunction "GND_1") (pintype "power_in"))
      (node (ref "GPS") (pin "10") (pinfunction "GND_10") (pintype "power_in"))
      (node (ref "GPS") (pin "11") (pinfunction "GND_11") (pintype "power_in"))
      (node (ref "GPS") (pin "15") (pinfunction "GND_15") (pintype "power_in"))
      (node (ref "GPS") (pin "16") (pinfunction "GND_16") (pintype "power_in"))
      (node (ref "GPS") (pin "20") (pinfunction "GND_20") (pintype "power_in"))
      (node (ref "GPS") (pin "4") (pinfunction "GND_4") (pintype "power_in"))
      (node (ref "GPS") (pin "5") (pinfunction "GND_5") (pintype "power_in"))
      (node (ref "GPS") (pin "6") (pinfunction "GND_6") (pintype "power_in"))
      (node (ref "IMU1") (pin "17") (pinfunction "COM3_17") (pintype "input"))
      (node (ref "IMU1") (pin "18") (pinfunction "COM2_18") (pintype "bidirectional"))
      (node (ref "IMU1") (pin "2") (pinfunction "GND_2") (pintype "power_in"))
      (node (ref "IMU1") (pin "25") (pinfunction "GNDIO_25") (pintype "power_in"))
      (node (ref "IMU1") (pin "5") (pinfunction "PS1_5") (pintype "input"))
      (node (ref "IMU1") (pin "6") (pinfunction "PS0_6") (pintype "input"))
      (node (ref "IMU2") (pin "2") (pinfunction "NC_2") (pintype "passive"))
      (node (ref "IMU2") (pin "4") (pinfunction "GNDA_4") (pintype "power_in"))
      (node (ref "IMU2") (pin "6") (pinfunction "GNDIO_6") (pintype "power_in"))
      (node (ref "IMU2") (pin "7") (pinfunction "PS_7") (pintype "input"))
      (node (ref "J1") (pin "2") (pinfunction "NEG_2") (pintype "passive"))
      (node (ref "LoRa Misc") (pin "3") (pinfunction "3_3") (pintype "passive"))
      (node (ref "MCU") (pin "107") (pinfunction "VSS_107") (pintype "input"))
      (node (ref "MCU") (pin "121") (pinfunction "VSS_121") (pintype "input"))
      (node (ref "MCU") (pin "134") (pinfunction "VSS_134") (pintype "input"))
      (node (ref "MCU") (pin "17") (pinfunction "VSS_17") (pintype "input"))
      (node (ref "MCU") (pin "18") (pinfunction "VSS_18") (pintype "input"))
      (node (ref "MCU") (pin "44") (pinfunction "VSS_44") (pintype "input"))
      (node (ref "MCU") (pin "57") (pinfunction "VSS_57") (pintype "input"))
      (node (ref "MCU") (pin "6") (pinfunction "VSS_6") (pintype "input"))
      (node (ref "MCU") (pin "71") (pinfunction "VSS_71") (pintype "input"))
      (node (ref "MCU") (pin "93") (pinfunction "VSS_93") (pintype "input"))
      (node (ref "MUX") (pin "17") (pinfunction "EP_17") (pintype "passive"))
      (node (ref "MUX") (pin "5") (pinfunction "A_5") (pintype "passive"))
      (node (ref "MUX") (pin "8") (pinfunction "GND_8") (pintype "passive"))
      (node (ref "NRF Misc") (pin "3") (pinfunction "3_3") (pintype "passive"))
      (node (ref "PWM DRIVER") (pin "14") (pinfunction "VSS_14") (pintype "power_in"))
      (node (ref "PWM DRIVER") (pin "25") (pinfunction "EXTCLK_25") (pintype "input"))
      (node (ref "Primary Connector") (pin "23") (pinfunction "23_23") (pintype "passive"))
      (node (ref "Primary Connector") (pin "48") (pinfunction "48_48") (pintype "passive"))
      (node (ref "Q10") (pin "2") (pinfunction "S_2") (pintype "passive"))
      (node (ref "R105") (pin "2") (pinfunction "2_2") (pintype "passive"))
      (node (ref "R107") (pin "2") (pinfunction "2_2") (pintype "passive"))
      (node (ref "R307") (pin "2") (pinfunction "2_2") (pintype "passive"))
      (node (ref "R502") (pin "1") (pinfunction "1_1") (pintype "passive"))
      (node (ref "R503") (pin "1") (pinfunction "1_1") (pintype "passive"))
      (node (ref "R602") (pin "1") (pinfunction "1_1") (pintype "passive"))
      (node (ref "RS-485") (pin "4") (pinfunction "GND_4") (pintype "passive"))
      (node (ref "SD") (pin "11") (pinfunction "SHLD1_11") (pintype "passive"))
      (node (ref "SD") (pin "12") (pinfunction "SHLD2_12") (pintype "passive"))
      (node (ref "SD") (pin "6") (pinfunction "VSS2_6") (pintype "passive"))
      (node (ref "Secondary Connector") (pin "11") (pinfunction "11_11") (pintype "passive"))
      (node (ref "Secondary Connector") (pin "15") (pinfunction "15_15") (pintype "passive"))
      (node (ref "Secondary Connector") (pin "18") (pinfunction "18_18") (pintype "passive"))
      (node (ref "Secondary Connector") (pin "2") (pinfunction "2_2") (pintype "passive"))
      (node (ref "Secondary Connector") (pin "21") (pinfunction "21_21") (pintype "passive"))
      (node (ref "Secondary Connector") (pin "24") (pinfunction "24_24") (pintype "passive"))
      (node (ref "Secondary Connector") (pin "5") (pinfunction "5_5") (pintype "passive"))
      (node (ref "Secondary Connector") (pin "8") (pinfunction "8_8") (pintype "passive"))
      (node (ref "USB") (pin "10") (pinfunction "SHLD5_10") (pintype "passive"))
      (node (ref "USB") (pin "11") (pinfunction "SHLD6_11") (pintype "passive"))
      (node (ref "USB") (pin "5") (pinfunction "GND_5") (pintype "passive"))
      (node (ref "USB") (pin "6") (pinfunction "SHLD1_6") (pintype "passive"))
      (node (ref "USB") (pin "7") (pinfunction "SHLD2_7") (pintype "passive"))
      (node (ref "USB") (pin "8") (pinfunction "SHLD3_8") (pintype "passive"))
      (node (ref "USB") (pin "9") (pinfunction "SHLD4_9") (pintype "passive"))
      (node (ref "Y1") (pin "2") (pinfunction "GND_2") (pintype "power_in"))
      (node (ref "Y1") (pin "4") (pinfunction "GND_4") (pintype "power_in"))
    )
    (net (code "188") (name "Net-(3.3V-INPUT)") (class "Default")
      (node (ref "3.3V") (pin "3") (pinfunction "INPUT_3") (pintype "passive"))
      (node (ref "5V") (pin "1") (pinfunction "INPUT_1") (pintype "passive"))
      (node (ref "C103") (pin "2") (pinfunction "2_2") (pintype "passive"))
      (node (ref "C105") (pin "2") (pinfunction "2_2") (pintype "passive"))
      (node (ref "D1") (pin "1") (pinfunction "C_1") (pintype "passive"))
    )
    (net (code "189") (name "Net-(BUCK-+VOUT)") (class "Default")
      (node (ref "BUCK") (pin "3") (pinfunction "+VOUT_3") (pintype "passive"))
      (node (ref "C102") (pin "2") (pinfunction "2_2") (pintype "passive"))
      (node (ref "D2") (pin "1") (pinfunction "C_1") (pintype "passive"))
      (node (ref "F1") (pin "1") (pinfunction "1_1") (pintype "passive"))
    )
    (net (code "190") (name "Net-(BUZZER--POLARITY)") (class "Default")
      (node (ref "BUZZER") (pin "3") (pinfunction "-POLARITY_3") (pintype "passive"))
      (node (ref "R601") (pin "2") (pinfunction "2_2") (pintype "passive"))
    )
    (net (code "191") (name "Net-(CAN2 TRAN-RS)") (class "Default")
      (node (ref "CAN2 TRAN") (pin "8") (pinfunction "RS_8") (pintype "input"))
      (node (ref "R307") (pin "1") (pinfunction "1_1") (pintype "passive"))
    )
    (net (code "192") (name "Net-(D1-A)") (class "Default")
      (node (ref "D1") (pin "2") (pinfunction "A_2") (pintype "passive"))
      (node (ref "FB1") (pin "2") (pinfunction "2_2") (pintype "passive"))
    )
    (net (code "193") (name "Net-(DS1-A)") (class "Default")
      (node (ref "DS1") (pin "2") (pinfunction "A_2") (pintype "passive"))
      (node (ref "R101") (pin "1") (pinfunction "1_1") (pintype "passive"))
    )
    (net (code "194") (name "Net-(DS2-A)") (class "Default")
      (node (ref "DS2") (pin "2") (pinfunction "A_2") (pintype "passive"))
      (node (ref "R102") (pin "1") (pinfunction "1_1") (pintype "passive"))
    )
    (net (code "195") (name "Net-(DS3-A)") (class "Default")
      (node (ref "DS3") (pin "2") (pinfunction "A_2") (pintype "passive"))
      (node (ref "R103") (pin "1") (pinfunction "1_1") (pintype "passive"))
    )
    (net (code "196") (name "Net-(DS4-A)") (class "Default")
      (node (ref "DS4") (pin "2") (pinfunction "A_2") (pintype "passive"))
      (node (ref "R401") (pin "2") (pinfunction "2_2") (pintype "passive"))
    )
    (net (code "197") (name "Net-(F1-Pad2)") (class "Default")
      (node (ref "F1") (pin "2") (pinfunction "2_2") (pintype "passive"))
      (node (ref "FB1") (pin "1") (pinfunction "1_1") (pintype "passive"))
    )
    (net (code "198") (name "Net-(GPS-EXTINT)") (class "Default")
      (node (ref "FB8") (pin "1") (pinfunction "1_1") (pintype "passive"))
      (node (ref "GPS") (pin "19") (pinfunction "EXTINT_19") (pintype "input"))
    )
    (net (code "199") (name "Net-(GPS-SCL)") (class "Default")
      (node (ref "FB6") (pin "2") (pinfunction "2_2") (pintype "passive"))
      (node (ref "GPS") (pin "12") (pinfunction "SCL_12") (pintype "input"))
    )
    (net (code "200") (name "Net-(GPS-SDA)") (class "Default")
      (node (ref "FB7") (pin "2") (pinfunction "2_2") (pintype "passive"))
      (node (ref "GPS") (pin "9") (pinfunction "SDA_9") (pintype "bidirectional"))
    )
    (net (code "201") (name "Net-(GPS-TIMEPULSE)") (class "Default")
      (node (ref "FB9") (pin "1") (pinfunction "1_1") (pintype "passive"))
      (node (ref "GPS") (pin "7") (pinfunction "TIMEPULSE_7") (pintype "output"))
    )
    (net (code "202") (name "Net-(GPS-~{RESET})") (class "Default")
      (node (ref "FB5") (pin "2") (pinfunction "2_2") (pintype "passive"))
      (node (ref "GPS") (pin "18") (pinfunction "~{RESET}_18") (pintype "input"))
    )
    (net (code "203") (name "Net-(IMU1-CAP)") (class "Default")
      (node (ref "C406") (pin "2") (pinfunction "2_2") (pintype "passive"))
      (node (ref "IMU1") (pin "9") (pinfunction "CAP_9") (pintype "passive"))
    )
    (net (code "204") (name "Net-(IMU1-~{BOOT_LOAD_PIN})") (class "Default")
      (node (ref "IMU1") (pin "4") (pinfunction "~{BOOT_LOAD_PIN}_4") (pintype "input"))
      (node (ref "R406") (pin "1") (pinfunction "1_1") (pintype "passive"))
    )
    (net (code "205") (name "Net-(Q10-D)") (class "Default")
      (node (ref "Q10") (pin "3") (pinfunction "D_3") (pintype "passive"))
      (node (ref "R601") (pin "1") (pinfunction "1_1") (pintype "passive"))
    )
    (net (code "206") (name "unconnected-(ACC-INT1-Pad5)") (class "Default")
      (node (ref "ACC") (pin "5") (pinfunction "INT1_5") (pintype "input+no_connect"))
    )
    (net (code "207") (name "unconnected-(ACC-INT2-Pad6)") (class "Default")
      (node (ref "ACC") (pin "6") (pinfunction "INT2_6") (pintype "input+no_connect"))
    )
    (net (code "208") (name "unconnected-(ACC-NC-Pad11)") (class "Default")
      (node (ref "ACC") (pin "11") (pinfunction "NC_11") (pintype "passive+no_connect"))
    )
    (net (code "209") (name "unconnected-(BOOT-PTA0{slash}IRQ_0-Pad14)") (class "Default")
      (node (ref "BOOT") (pin "14") (pinfunction "PTA0/IRQ_0_14") (pintype "passive+no_connect"))
    )
    (net (code "210") (name "unconnected-(BOOT-PTA1{slash}IRQ_1{slash}LPTMR0_ALT1-Pad15)") (class "Default")
      (node (ref "BOOT") (pin "15") (pinfunction "PTA1/IRQ_1/LPTMR0_ALT1_15") (pintype "passive+no_connect"))
    )
    (net (code "211") (name "unconnected-(BOOT-PTA2-Pad16)") (class "Default")
      (node (ref "BOOT") (pin "16") (pinfunction "PTA2_16") (pintype "passive+no_connect"))
    )
    (net (code "212") (name "unconnected-(BOOT-PTA5-Pad5)") (class "Default")
      (node (ref "BOOT") (pin "5") (pinfunction "PTA5_5") (pintype "passive+no_connect"))
    )
    (net (code "213") (name "unconnected-(BOOT-PTB3{slash}IRQ_10-Pad11)") (class "Default")
      (node (ref "BOOT") (pin "11") (pinfunction "PTB3/IRQ_10_11") (pintype "passive+no_connect"))
    )
    (net (code "214") (name "unconnected-(BOOT-PTB4{slash}IRQ_11-Pad12)") (class "Default")
      (node (ref "BOOT") (pin "12") (pinfunction "PTB4/IRQ_11_12") (pintype "passive+no_connect"))
    )
    (net (code "215") (name "unconnected-(BUZZER-NC-Pad1)") (class "Default")
      (node (ref "BUZZER") (pin "1") (pinfunction "NC_1") (pintype "passive+no_connect"))
    )
    (net (code "216") (name "unconnected-(BUZZER-NC-Pad4)") (class "Default")
      (node (ref "BUZZER") (pin "4") (pinfunction "NC_4") (pintype "passive+no_connect"))
    )
    (net (code "217") (name "unconnected-(CAN2 TRAN-VREF-Pad5)") (class "Default")
      (node (ref "CAN2 TRAN") (pin "5") (pinfunction "VREF_5") (pintype "output"))
    )
    (net (code "218") (name "unconnected-(DEMUX-NC-Pad6)") (class "Default")
      (node (ref "DEMUX") (pin "6") (pinfunction "NC_6") (pintype "passive+no_connect"))
    )
    (net (code "219") (name "unconnected-(GPS-RXD-Pad14)") (class "Default")
      (node (ref "GPS") (pin "14") (pinfunction "RXD_14") (pintype "input+no_connect"))
    )
    (net (code "220") (name "unconnected-(GPS-TXD-Pad13)") (class "Default")
      (node (ref "GPS") (pin "13") (pinfunction "TXD_13") (pintype "output+no_connect"))
    )
    (net (code "221") (name "unconnected-(GPS-~{SAFEBOOT}-Pad8)") (class "Default")
      (node (ref "GPS") (pin "8") (pinfunction "~{SAFEBOOT}_8") (pintype "input+no_connect"))
    )
    (net (code "222") (name "unconnected-(IMU1-BL_IND-Pad10)") (class "Default")
      (node (ref "IMU1") (pin "10") (pinfunction "BL_IND_10") (pintype "output+no_connect"))
    )
    (net (code "223") (name "unconnected-(IMU1-INT-Pad14)") (class "Default")
      (node (ref "IMU1") (pin "14") (pinfunction "INT_14") (pintype "passive+no_connect"))
    )
    (net (code "224") (name "unconnected-(IMU1-NC-Pad1)") (class "Default")
      (node (ref "IMU1") (pin "1") (pinfunction "NC_1") (pintype "passive+no_connect"))
    )
    (net (code "225") (name "unconnected-(IMU1-NC-Pad12)") (class "Default")
      (node (ref "IMU1") (pin "12") (pinfunction "NC_12") (pintype "passive+no_connect"))
    )
    (net (code "226") (name "unconnected-(IMU1-NC-Pad13)") (class "Default")
      (node (ref "IMU1") (pin "13") (pinfunction "NC_13") (pintype "passive+no_connect"))
    )
    (net (code "227") (name "unconnected-(IMU1-NC-Pad15)") (class "Default")
      (node (ref "IMU1") (pin "15") (pinfunction "NC_15") (pintype "passive+no_connect"))
    )
    (net (code "228") (name "unconnected-(IMU1-NC-Pad16)") (class "Default")
      (node (ref "IMU1") (pin "16") (pinfunction "NC_16") (pintype "passive+no_connect"))
    )
    (net (code "229") (name "unconnected-(IMU1-NC-Pad21)") (class "Default")
      (node (ref "IMU1") (pin "21") (pinfunction "NC_21") (pintype "passive+no_connect"))
    )
    (net (code "230") (name "unconnected-(IMU1-NC-Pad22)") (class "Default")
      (node (ref "IMU1") (pin "22") (pinfunction "NC_22") (pintype "passive+no_connect"))
    )
    (net (code "231") (name "unconnected-(IMU1-NC-Pad23)") (class "Default")
      (node (ref "IMU1") (pin "23") (pinfunction "NC_23") (pintype "passive+no_connect"))
    )
    (net (code "232") (name "unconnected-(IMU1-NC-Pad24)") (class "Default")
      (node (ref "IMU1") (pin "24") (pinfunction "NC_24") (pintype "passive+no_connect"))
    )
    (net (code "233") (name "unconnected-(IMU1-SWCLK-Pad8)") (class "Default")
      (node (ref "IMU1") (pin "8") (pinfunction "SWCLK_8") (pintype "input+no_connect"))
    )
    (net (code "234") (name "unconnected-(IMU1-SWDIO-Pad7)") (class "Default")
      (node (ref "IMU1") (pin "7") (pinfunction "SWDIO_7") (pintype "bidirectional+no_connect"))
    )
    (net (code "235") (name "unconnected-(IMU1-XIN32-Pad27)") (class "Default")
      (node (ref "IMU1") (pin "27") (pinfunction "XIN32_27") (pintype "input+no_connect"))
    )
    (net (code "236") (name "unconnected-(IMU1-XOUT32-Pad26)") (class "Default")
      (node (ref "IMU1") (pin "26") (pinfunction "XOUT32_26") (pintype "passive+no_connect"))
    )
    (net (code "237") (name "unconnected-(IMU2-INT1-Pad16)") (class "Default")
      (node (ref "IMU2") (pin "16") (pinfunction "INT1_16") (pintype "output+no_connect"))
    )
    (net (code "238") (name "unconnected-(IMU2-INT2-Pad1)") (class "Default")
      (node (ref "IMU2") (pin "1") (pinfunction "INT2_1") (pintype "output+no_connect"))
    )
    (net (code "239") (name "unconnected-(IMU2-INT3-Pad12)") (class "Default")
      (node (ref "IMU2") (pin "12") (pinfunction "INT3_12") (pintype "output+no_connect"))
    )
    (net (code "240") (name "unconnected-(IMU2-INT4-Pad13)") (class "Default")
      (node (ref "IMU2") (pin "13") (pinfunction "INT4_13") (pintype "output+no_connect"))
    )
    (net (code "241") (name "unconnected-(MCU-ADC0_DM0{slash}ADC1_DM3-Pad28)") (class "Default")
      (node (ref "MCU") (pin "28") (pinfunction "ADC0_DM0/ADC1_DM3_28") (pintype "input+no_connect"))
    )
    (net (code "242") (name "unconnected-(MCU-ADC0_SE16{slash}CMP1_IN2{slash}ADC0_SE21-Pad36)") (class "Default")
      (node (ref "MCU") (pin "36") (pinfunction "ADC0_SE16/CMP1_IN2/ADC0_SE21_36") (pintype "input+no_connect"))
    )
    (net (code "243") (name "unconnected-(MCU-ADC1_SE16{slash}CMP2_IN2{slash}ADC0_SE22-Pad35)") (class "Default")
      (node (ref "MCU") (pin "35") (pinfunction "ADC1_SE16/CMP2_IN2/ADC0_SE22_35") (pintype "input+no_connect"))
    )
    (net (code "244") (name "unconnected-(MCU-PTA6-Pad58)") (class "Default")
      (node (ref "MCU") (pin "58") (pinfunction "PTA6_58") (pintype "input+no_connect"))
    )
    (net (code "245") (name "unconnected-(MCU-PTA7-Pad59)") (class "Default")
      (node (ref "MCU") (pin "59") (pinfunction "PTA7_59") (pintype "input+no_connect"))
    )
    (net (code "246") (name "unconnected-(MCU-PTA8-Pad60)") (class "Default")
      (node (ref "MCU") (pin "60") (pinfunction "PTA8_60") (pintype "input+no_connect"))
    )
    (net (code "247") (name "unconnected-(MCU-PTA9-Pad61)") (class "Default")
      (node (ref "MCU") (pin "61") (pinfunction "PTA9_61") (pintype "input+no_connect"))
    )
    (net (code "248") (name "unconnected-(MCU-PTA10{slash}LLWU_P22-Pad62)") (class "Default")
      (node (ref "MCU") (pin "62") (pinfunction "PTA10/LLWU_P22_62") (pintype "input+no_connect"))
    )
    (net (code "249") (name "unconnected-(MCU-PTA11{slash}LLWU_P23-Pad63)") (class "Default")
      (node (ref "MCU") (pin "63") (pinfunction "PTA11/LLWU_P23_63") (pintype "input+no_connect"))
    )
    (net (code "250") (name "unconnected-(MCU-PTA27-Pad78)") (class "Default")
      (node (ref "MCU") (pin "78") (pinfunction "PTA27_78") (pintype "input+no_connect"))
    )
    (net (code "251") (name "unconnected-(MCU-PTB6-Pad87)") (class "Default")
      (node (ref "MCU") (pin "87") (pinfunction "PTB6_87") (pintype "input+no_connect"))
    )
    (net (code "252") (name "unconnected-(MCU-PTB7-Pad88)") (class "Default")
      (node (ref "MCU") (pin "88") (pinfunction "PTB7_88") (pintype "input+no_connect"))
    )
    (net (code "253") (name "unconnected-(MCU-PTB8-Pad89)") (class "Default")
      (node (ref "MCU") (pin "89") (pinfunction "PTB8_89") (pintype "input+no_connect"))
    )
    (net (code "254") (name "unconnected-(MCU-PTB18-Pad97)") (class "Default")
      (node (ref "MCU") (pin "97") (pinfunction "PTB18_97") (pintype "input+no_connect"))
    )
    (net (code "255") (name "unconnected-(MCU-USB1_DM-Pad26)") (class "Default")
      (node (ref "MCU") (pin "26") (pinfunction "USB1_DM_26") (pintype "input+no_connect"))
    )
    (net (code "256") (name "unconnected-(MCU-USB1_DP-Pad25)") (class "Default")
      (node (ref "MCU") (pin "25") (pinfunction "USB1_DP_25") (pintype "input+no_connect"))
    )
    (net (code "257") (name "unconnected-(MCU-USB1_VBUS-Pad27)") (class "Default")
      (node (ref "MCU") (pin "27") (pinfunction "USB1_VBUS_27") (pintype "input+no_connect"))
    )
    (net (code "258") (name "unconnected-(MCU-USB1_VSS-Pad24)") (class "Default")
      (node (ref "MCU") (pin "24") (pinfunction "USB1_VSS_24") (pintype "input+no_connect"))
    )
    (net (code "259") (name "unconnected-(MCU-VREG_IN0-Pad22)") (class "Default")
      (node (ref "MCU") (pin "22") (pinfunction "VREG_IN0_22") (pintype "input+no_connect"))
    )
    (net (code "260") (name "unconnected-(MCU-VREG_IN1-Pad23)") (class "Default")
      (node (ref "MCU") (pin "23") (pinfunction "VREG_IN1_23") (pintype "input+no_connect"))
    )
    (net (code "261") (name "unconnected-(MUX-NC-Pad6)") (class "Default")
      (node (ref "MUX") (pin "6") (pinfunction "NC_6") (pintype "passive+no_connect"))
    )
    (net (code "262") (name "unconnected-(PWM DRIVER-LED6-Pad12)") (class "Default")
      (node (ref "PWM DRIVER") (pin "12") (pinfunction "LED6_12") (pintype "tri_state"))
    )
    (net (code "263") (name "unconnected-(PWM DRIVER-LED7-Pad13)") (class "Default")
      (node (ref "PWM DRIVER") (pin "13") (pinfunction "LED7_13") (pintype "tri_state"))
    )
    (net (code "264") (name "unconnected-(PWM DRIVER-LED8-Pad15)") (class "Default")
      (node (ref "PWM DRIVER") (pin "15") (pinfunction "LED8_15") (pintype "tri_state"))
    )
    (net (code "265") (name "unconnected-(PWM DRIVER-LED9-Pad16)") (class "Default")
      (node (ref "PWM DRIVER") (pin "16") (pinfunction "LED9_16") (pintype "tri_state"))
    )
    (net (code "266") (name "unconnected-(PWM DRIVER-LED10-Pad17)") (class "Default")
      (node (ref "PWM DRIVER") (pin "17") (pinfunction "LED10_17") (pintype "tri_state"))
    )
    (net (code "267") (name "unconnected-(PWM DRIVER-LED11-Pad18)") (class "Default")
      (node (ref "PWM DRIVER") (pin "18") (pinfunction "LED11_18") (pintype "tri_state"))
    )
    (net (code "268") (name "unconnected-(PWM DRIVER-LED12-Pad19)") (class "Default")
      (node (ref "PWM DRIVER") (pin "19") (pinfunction "LED12_19") (pintype "tri_state"))
    )
    (net (code "269") (name "unconnected-(PWM DRIVER-LED13-Pad20)") (class "Default")
      (node (ref "PWM DRIVER") (pin "20") (pinfunction "LED13_20") (pintype "tri_state"))
    )
    (net (code "270") (name "unconnected-(PWM DRIVER-LED14-Pad21)") (class "Default")
      (node (ref "PWM DRIVER") (pin "21") (pinfunction "LED14_21") (pintype "tri_state"))
    )
    (net (code "271") (name "unconnected-(PWM DRIVER-LED15-Pad22)") (class "Default")
      (node (ref "PWM DRIVER") (pin "22") (pinfunction "LED15_22") (pintype "tri_state"))
    )
    (net (code "272") (name "unconnected-(SD-CD_A-Pad9)") (class "Default")
      (node (ref "SD") (pin "9") (pinfunction "CD_A_9") (pintype "passive+no_connect"))
    )
    (net (code "273") (name "unconnected-(SD-CD_B-Pad10)") (class "Default")
      (node (ref "SD") (pin "10") (pinfunction "CD_B_10") (pintype "passive+no_connect"))
    )
    (net (code "274") (name "unconnected-(USB-ID-Pad4)") (class "Default")
      (node (ref "USB") (pin "4") (pinfunction "ID_4") (pintype "passive+no_connect"))
    )
  )
)
